# GD32F450.net
KiCad netlist of a schematic drawn in EAGLE
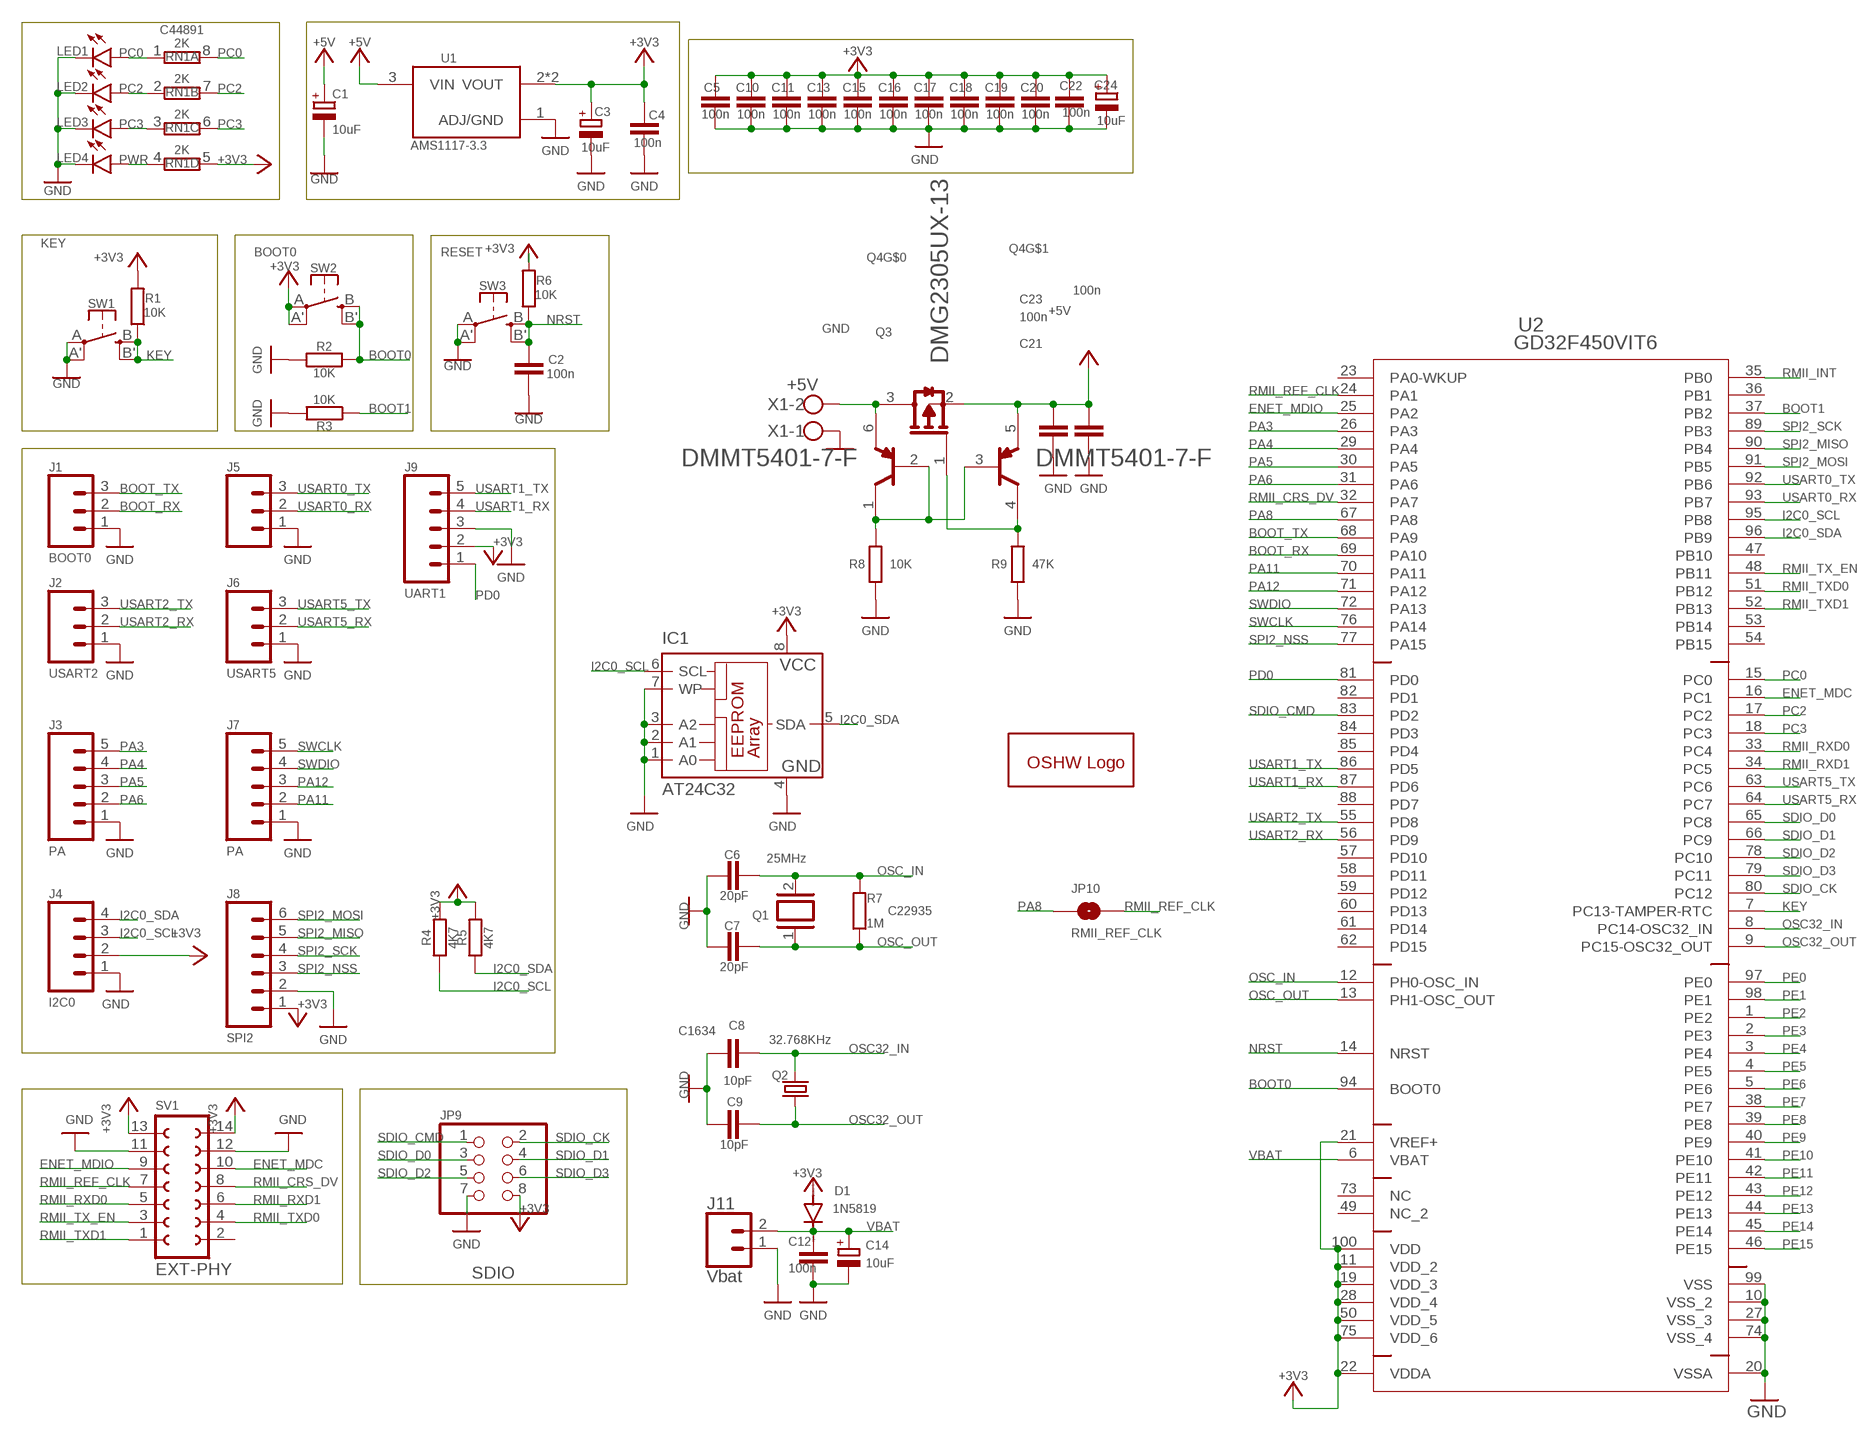
[diagram p0: schematic, sheet 1, part 1 of 2]
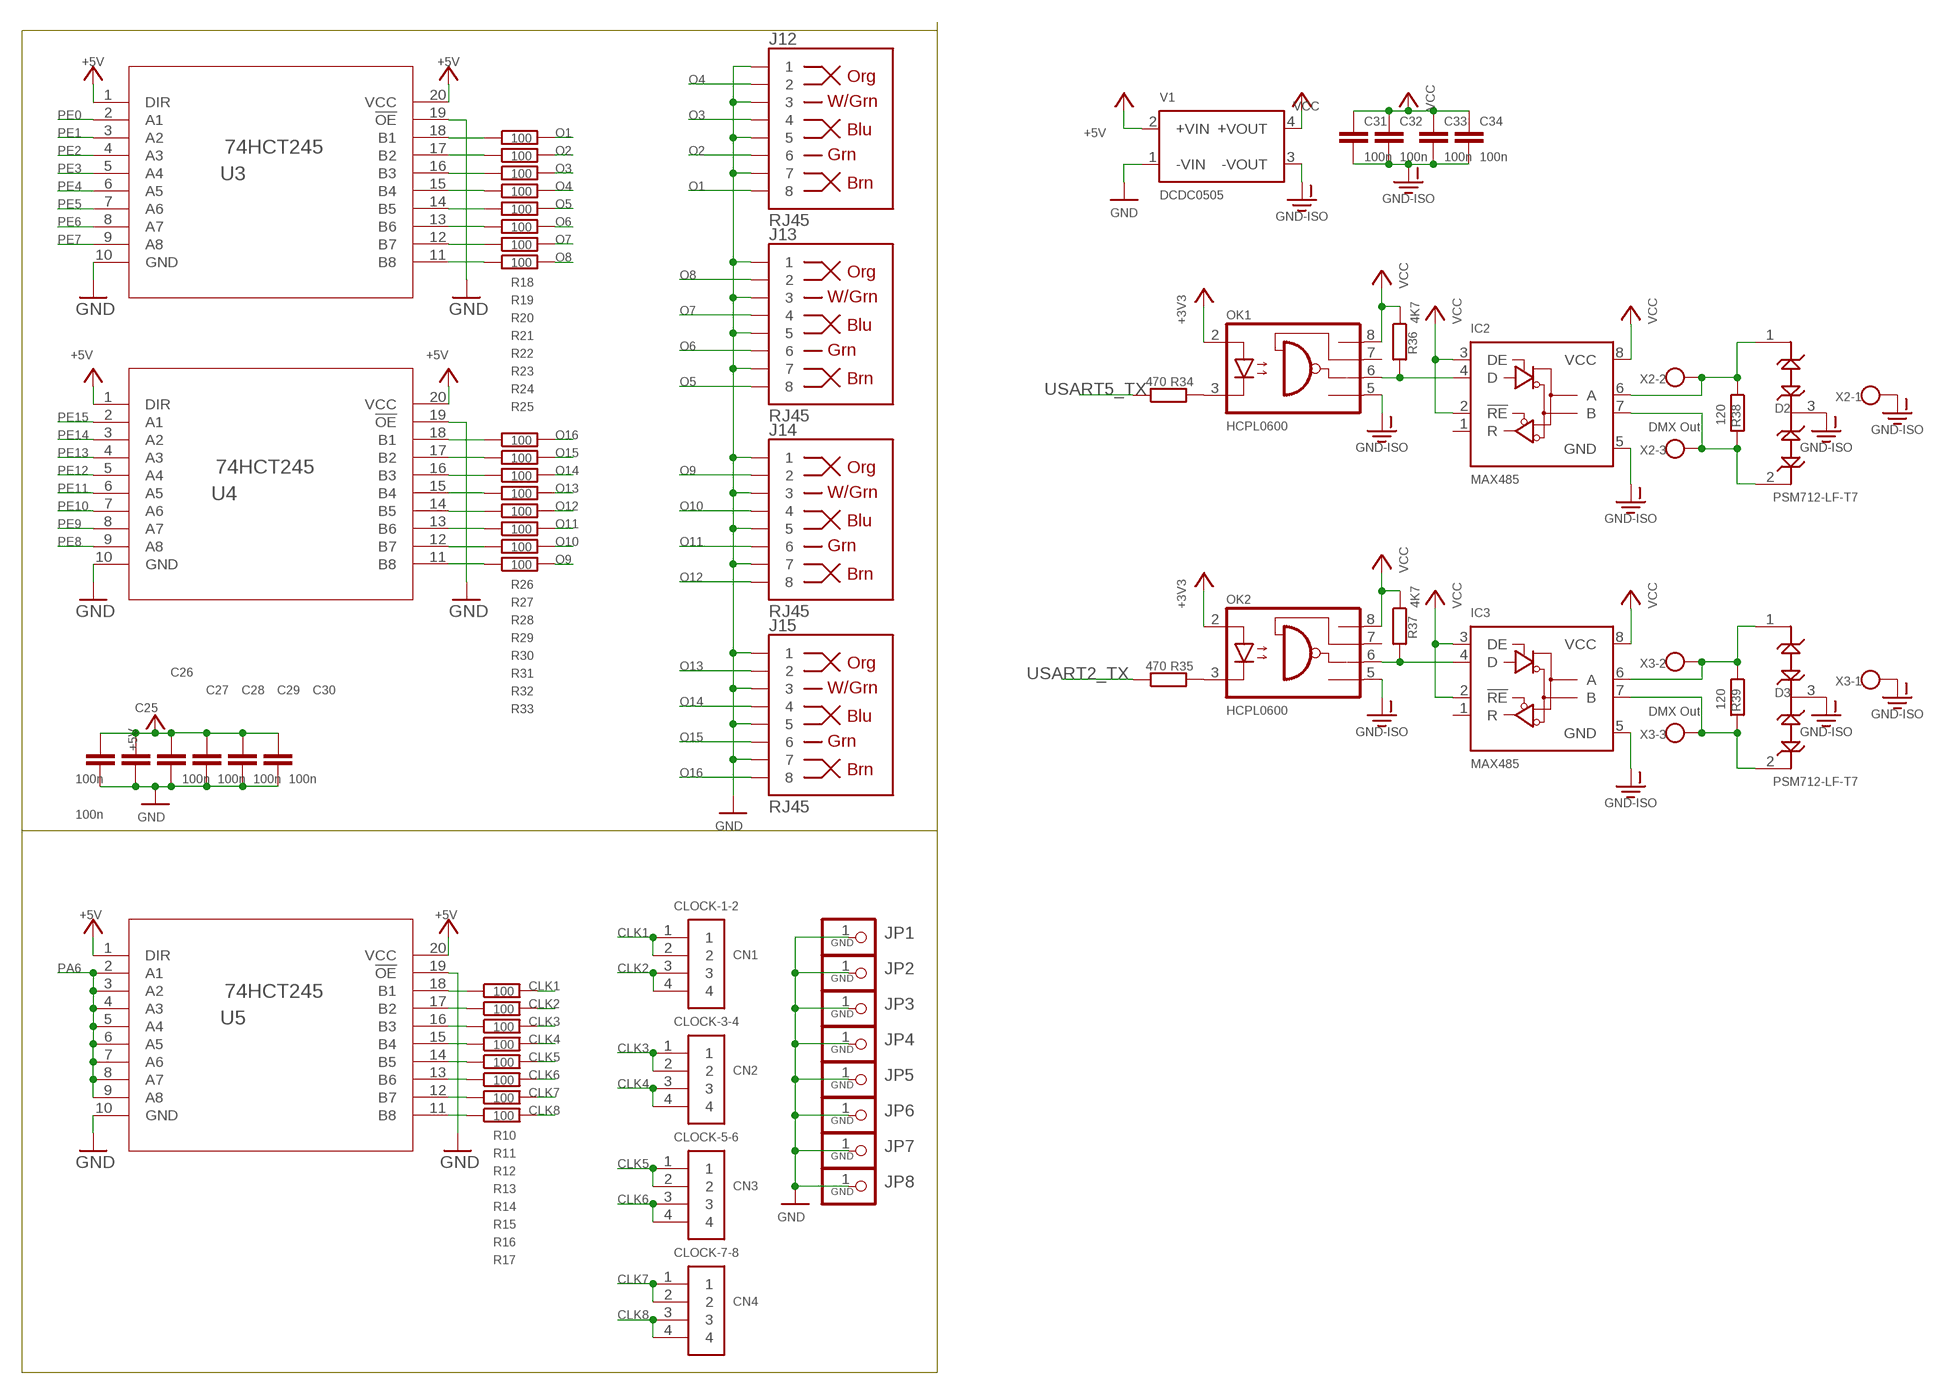
[diagram p1: schematic, sheet 1, part 2 of 2]

(export (version "E")
  (design (tool "Eeschema 10.0.6"))
  (components
    (comp (ref "C1")
      (value "10uF")
      (footprint "eagle-import:A_3216-18R")
      (libsource (lib "eagle-import") (part "CPOL-EUA/3216-18R"))
    )
    (comp (ref "C2")
      (value "100n")
      (footprint "eagle-import:C0603")
      (libsource (lib "eagle-import") (part "C-EUC0603"))
    )
    (comp (ref "C3")
      (value "10uF")
      (footprint "eagle-import:A_3216-18R")
      (libsource (lib "eagle-import") (part "CPOL-EUA/3216-18R"))
    )
    (comp (ref "C4")
      (value "100n")
      (footprint "eagle-import:C0603")
      (libsource (lib "eagle-import") (part "C-EUC0603"))
    )
    (comp (ref "C5")
      (value "100n")
      (footprint "eagle-import:C0603")
      (libsource (lib "eagle-import") (part "C-EUC0603"))
    )
    (comp (ref "C6")
      (value "20pF")
      (footprint "eagle-import:C0603")
      (libsource (lib "eagle-import") (part "C-EUC0603"))
    )
    (comp (ref "C7")
      (value "20pF")
      (footprint "eagle-import:C0603")
      (libsource (lib "eagle-import") (part "C-EUC0603"))
    )
    (comp (ref "C8")
      (value "10pF")
      (footprint "eagle-import:C0603")
      (fields (field (name "JLCPCB") "C1634"))
      (libsource (lib "eagle-import") (part "C-EUC0603"))
    )
    (comp (ref "C9")
      (value "10pF")
      (footprint "eagle-import:C0603")
      (libsource (lib "eagle-import") (part "C-EUC0603"))
    )
    (comp (ref "C10")
      (value "100n")
      (footprint "eagle-import:C0603")
      (libsource (lib "eagle-import") (part "C-EUC0603"))
    )
    (comp (ref "C11")
      (value "100n")
      (footprint "eagle-import:C0603")
      (libsource (lib "eagle-import") (part "C-EUC0603"))
    )
    (comp (ref "C12")
      (value "100n")
      (footprint "eagle-import:C0603")
      (libsource (lib "eagle-import") (part "C-EUC0603"))
    )
    (comp (ref "C13")
      (value "100n")
      (footprint "eagle-import:C0603")
      (libsource (lib "eagle-import") (part "C-EUC0603"))
    )
    (comp (ref "C14")
      (value "10uF")
      (footprint "eagle-import:A_3216-18R")
      (libsource (lib "eagle-import") (part "CPOL-EUA/3216-18R"))
    )
    (comp (ref "C15")
      (value "100n")
      (footprint "eagle-import:C0603")
      (libsource (lib "eagle-import") (part "C-EUC0603"))
    )
    (comp (ref "C16")
      (value "100n")
      (footprint "eagle-import:C0603")
      (libsource (lib "eagle-import") (part "C-EUC0603"))
    )
    (comp (ref "C17")
      (value "100n")
      (footprint "eagle-import:C0603")
      (libsource (lib "eagle-import") (part "C-EUC0603"))
    )
    (comp (ref "C18")
      (value "100n")
      (footprint "eagle-import:C0603")
      (libsource (lib "eagle-import") (part "C-EUC0603"))
    )
    (comp (ref "C19")
      (value "100n")
      (footprint "eagle-import:C0603")
      (libsource (lib "eagle-import") (part "C-EUC0603"))
    )
    (comp (ref "C20")
      (value "100n")
      (footprint "eagle-import:C0603")
      (libsource (lib "eagle-import") (part "C-EUC0603"))
    )
    (comp (ref "C21")
      (value "100n")
      (footprint "eagle-import:C0603")
      (libsource (lib "eagle-import") (part "C-EUC0603"))
    )
    (comp (ref "C22")
      (value "100n")
      (footprint "eagle-import:C0603")
      (libsource (lib "eagle-import") (part "C-EUC0603"))
    )
    (comp (ref "C23")
      (value "100n")
      (footprint "eagle-import:C0603")
      (libsource (lib "eagle-import") (part "C-EUC0603"))
    )
    (comp (ref "C24")
      (value "10uF")
      (footprint "eagle-import:A_3216-18R")
      (libsource (lib "eagle-import") (part "CPOL-EUA/3216-18R"))
    )
    (comp (ref "C25")
      (value "100n")
      (footprint "eagle-import:C0603")
      (libsource (lib "eagle-import") (part "C-EUC0603"))
    )
    (comp (ref "C26")
      (value "100n")
      (footprint "eagle-import:C0603")
      (libsource (lib "eagle-import") (part "C-EUC0603"))
    )
    (comp (ref "C27")
      (value "100n")
      (footprint "eagle-import:C0603")
      (libsource (lib "eagle-import") (part "C-EUC0603"))
    )
    (comp (ref "C28")
      (value "100n")
      (footprint "eagle-import:C0603")
      (libsource (lib "eagle-import") (part "C-EUC0603"))
    )
    (comp (ref "C29")
      (value "100n")
      (footprint "eagle-import:C0603")
      (libsource (lib "eagle-import") (part "C-EUC0603"))
    )
    (comp (ref "C30")
      (value "100n")
      (footprint "eagle-import:C0603")
      (libsource (lib "eagle-import") (part "C-EUC0603"))
    )
    (comp (ref "C31")
      (value "100n")
      (footprint "eagle-import:C0603")
      (libsource (lib "eagle-import") (part "C-EUC0603"))
    )
    (comp (ref "C32")
      (value "100n")
      (footprint "eagle-import:C0603")
      (libsource (lib "eagle-import") (part "C-EUC0603"))
    )
    (comp (ref "C33")
      (value "100n")
      (footprint "eagle-import:C0603")
      (libsource (lib "eagle-import") (part "C-EUC0603"))
    )
    (comp (ref "C34")
      (value "100n")
      (footprint "eagle-import:C0603")
      (libsource (lib "eagle-import") (part "C-EUC0603"))
    )
    (comp (ref "CN1")
      (value "CLOCK-1-2")
      (footprint "eagle-import:1X04-CLEANBIG")
      (libsource (lib "eagle-import") (part "1X4-CLEANBIG"))
    )
    (comp (ref "CN2")
      (value "CLOCK-3-4")
      (footprint "eagle-import:1X04-CLEANBIG")
      (libsource (lib "eagle-import") (part "1X4-CLEANBIG"))
    )
    (comp (ref "CN3")
      (value "CLOCK-5-6")
      (footprint "eagle-import:1X04-CLEANBIG")
      (libsource (lib "eagle-import") (part "1X4-CLEANBIG"))
    )
    (comp (ref "CN4")
      (value "CLOCK-7-8")
      (footprint "eagle-import:1X04-CLEANBIG")
      (libsource (lib "eagle-import") (part "1X4-CLEANBIG"))
    )
    (comp (ref "D1")
      (value "1N5819")
      (footprint "eagle-import:SOD323-R")
      (libsource (lib "eagle-import") (part "DIODE-SOD323-R"))
    )
    (comp (ref "D2")
      (value "PSM712-LF-T7")
      (footprint "eagle-import:SOT23-3")
      (libsource (lib "eagle-import") (part "2CH_BI_DIR_TVSSOT23"))
    )
    (comp (ref "D3")
      (value "PSM712-LF-T7")
      (footprint "eagle-import:SOT23-3")
      (libsource (lib "eagle-import") (part "2CH_BI_DIR_TVSSOT23"))
    )
    (comp (ref "GOLD_ORB_SM1")
      (value "OSHWLOGOLOGO5MM")
      (footprint "eagle-import:OSHW_5MM")
      (libsource (lib "eagle-import") (part "OSHWLOGOLOGO5MM"))
    )
    (comp (ref "IC1")
      (value "AT24C32")
      (footprint "eagle-import:SO-08M")
      (fields (field (name "MPN") "M24C04-WMN6P"))
      (libsource (lib "eagle-import") (part "24SMC04A"))
    )
    (comp (ref "IC2")
      (value "MAX485")
      (footprint "eagle-import:D_R-PDSO-G8")
      (libsource (lib "eagle-import") (part "75176AD"))
    )
    (comp (ref "IC3")
      (value "MAX485")
      (footprint "eagle-import:D_R-PDSO-G8")
      (libsource (lib "eagle-import") (part "75176AD"))
    )
    (comp (ref "J1")
      (value "BOOT0")
      (footprint "eagle-import:1X03")
      (libsource (lib "eagle-import") (part "CONN_03"))
    )
    (comp (ref "J2")
      (value "USART2")
      (footprint "eagle-import:1X03")
      (libsource (lib "eagle-import") (part "CONN_03"))
    )
    (comp (ref "J3")
      (value "PA")
      (footprint "eagle-import:1X05")
      (libsource (lib "eagle-import") (part "CONN_05"))
    )
    (comp (ref "J4")
      (value "I2C0")
      (footprint "eagle-import:1X04")
      (libsource (lib "eagle-import") (part "CONN_04"))
    )
    (comp (ref "J5")
      (value "USART0")
      (footprint "eagle-import:1X03")
      (libsource (lib "eagle-import") (part "CONN_03"))
    )
    (comp (ref "J6")
      (value "USART5")
      (footprint "eagle-import:1X03")
      (libsource (lib "eagle-import") (part "CONN_03"))
    )
    (comp (ref "J7")
      (value "PA")
      (footprint "eagle-import:1X05")
      (libsource (lib "eagle-import") (part "CONN_05"))
    )
    (comp (ref "J8")
      (value "SPI2")
      (footprint "eagle-import:1X06")
      (libsource (lib "eagle-import") (part "CONN_06SILK_FEMALE_PTH"))
    )
    (comp (ref "J9")
      (value "UART1")
      (footprint "eagle-import:1X05")
      (libsource (lib "eagle-import") (part "CONN_05"))
    )
    (comp (ref "J11")
      (value "Vbat")
      (footprint "eagle-import:1X02_NO_SILK")
      (libsource (lib "eagle-import") (part "CONN_021X02_NO_SILK"))
    )
    (comp (ref "J12")
      (value "RJ45")
      (footprint "eagle-import:RJ45-8")
      (libsource (lib "eagle-import") (part "RJ45-8"))
    )
    (comp (ref "J13")
      (value "RJ45")
      (footprint "eagle-import:RJ45-8")
      (libsource (lib "eagle-import") (part "RJ45-8"))
    )
    (comp (ref "J14")
      (value "RJ45")
      (footprint "eagle-import:RJ45-8")
      (libsource (lib "eagle-import") (part "RJ45-8"))
    )
    (comp (ref "J15")
      (value "RJ45")
      (footprint "eagle-import:RJ45-8")
      (libsource (lib "eagle-import") (part "RJ45-8"))
    )
    (comp (ref "JP1")
      (value "GND")
      (footprint "eagle-import:1X01-CLEANBIG")
      (libsource (lib "eagle-import") (part "PINHD-1X1CB"))
    )
    (comp (ref "JP2")
      (value "GND")
      (footprint "eagle-import:1X01-CLEANBIG")
      (libsource (lib "eagle-import") (part "PINHD-1X1CB"))
    )
    (comp (ref "JP3")
      (value "GND")
      (footprint "eagle-import:1X01-CLEANBIG")
      (libsource (lib "eagle-import") (part "PINHD-1X1CB"))
    )
    (comp (ref "JP4")
      (value "GND")
      (footprint "eagle-import:1X01-CLEANBIG")
      (libsource (lib "eagle-import") (part "PINHD-1X1CB"))
    )
    (comp (ref "JP5")
      (value "GND")
      (footprint "eagle-import:1X01-CLEANBIG")
      (libsource (lib "eagle-import") (part "PINHD-1X1CB"))
    )
    (comp (ref "JP6")
      (value "GND")
      (footprint "eagle-import:1X01-CLEANBIG")
      (libsource (lib "eagle-import") (part "PINHD-1X1CB"))
    )
    (comp (ref "JP7")
      (value "GND")
      (footprint "eagle-import:1X01-CLEANBIG")
      (libsource (lib "eagle-import") (part "PINHD-1X1CB"))
    )
    (comp (ref "JP8")
      (value "GND")
      (footprint "eagle-import:1X01-CLEANBIG")
      (libsource (lib "eagle-import") (part "PINHD-1X1CB"))
    )
    (comp (ref "JP9")
      (value "SDIO")
      (footprint "eagle-import:2X04")
      (libsource (lib "eagle-import") (part "PINHD-2X4"))
    )
    (comp (ref "JP10")
      (value "RMII_REF_CLK")
      (footprint "eagle-import:SMT-JUMPER_2_NO_NO-SILK")
      (libsource (lib "eagle-import") (part "JUMPER-SMT_2_NO_NO-SILK"))
    )
    (comp (ref "LED1")
      (value "PC0")
      (footprint "eagle-import:CHIP-LED0603")
      (libsource (lib "eagle-import") (part "LEDCHIP-LED0603"))
    )
    (comp (ref "LED2")
      (value "PC2")
      (footprint "eagle-import:CHIP-LED0603")
      (libsource (lib "eagle-import") (part "LEDCHIP-LED0603"))
    )
    (comp (ref "LED3")
      (value "PC3")
      (footprint "eagle-import:CHIP-LED0603")
      (libsource (lib "eagle-import") (part "LEDCHIP-LED0603"))
    )
    (comp (ref "LED4")
      (value "PWR")
      (footprint "eagle-import:CHIP-LED0603")
      (libsource (lib "eagle-import") (part "LEDCHIP-LED0603"))
    )
    (comp (ref "OK1")
      (value "HCPL0600")
      (footprint "eagle-import:SOIC08")
      (fields (field (name "MF") "AGILENT TECHNOLOGIES") (field (name "MPN") "HCPL-0600-000E"))
      (libsource (lib "eagle-import") (part "HCPL0600"))
    )
    (comp (ref "OK2")
      (value "HCPL0600")
      (footprint "eagle-import:SOIC08")
      (fields (field (name "MF") "AGILENT TECHNOLOGIES") (field (name "MPN") "HCPL-0600-000E"))
      (libsource (lib "eagle-import") (part "HCPL0600"))
    )
    (comp (ref "Q1")
      (value "25MHz")
      (footprint "eagle-import:QS")
      (libsource (lib "eagle-import") (part "XTAL/S"))
    )
    (comp (ref "Q2")
      (value "32.768KHz")
      (footprint "eagle-import:TC26H")
      (libsource (lib "eagle-import") (part "CRYSTALTC26H"))
    )
    (comp (ref "Q3")
      (value "DMG2305UX")
      (footprint "eagle-import:DIODES_INC._DMG2305UX-13_0")
      (fields
        (field (name "DIGIKEY_PART_NUMBER") "DMG2305UX-13DICT-ND")
        (field (name "MF") "Diodes Inc.")
        (field (name "MOUSER_PART_NUMBER") "621-DMG2305UX-13")
      )
      (libsource (lib "eagle-import") (part "DIODES_INC._DMG2305UX-13DIODES_INC._DMG2305UX-13_0_0"))
    )
    (comp (ref "Q4")
      (value "DMMT5401")
      (footprint "eagle-import:DIODES_DMMT5401-7-F_0")
      (fields
        (field (name "DIGIKEY_PART_NUMBER") "DMMT5401-FDICT-ND")
        (field (name "MF") "Diodes")
        (field (name "MOUSER_PART_NUMBER") "621-DMMT5401-7-F")
      )
      (libsource (lib "eagle-import") (part "DIODES_DMMT5401-7-FDIODES_DMMT5401-7-F_0_0"))
    )
    (comp (ref "R1")
      (value "10K")
      (footprint "eagle-import:R0603")
      (libsource (lib "eagle-import") (part "R-EU_R0603"))
    )
    (comp (ref "R2")
      (value "10K")
      (footprint "eagle-import:R0603")
      (libsource (lib "eagle-import") (part "R-EU_R0603"))
    )
    (comp (ref "R3")
      (value "10K")
      (footprint "eagle-import:R0603")
      (libsource (lib "eagle-import") (part "R-EU_R0603"))
    )
    (comp (ref "R4")
      (value "4K7")
      (footprint "eagle-import:R0402")
      (libsource (lib "eagle-import") (part "R-EU_R0402"))
    )
    (comp (ref "R5")
      (value "4K7")
      (footprint "eagle-import:R0402")
      (libsource (lib "eagle-import") (part "R-EU_R0402"))
    )
    (comp (ref "R6")
      (value "10K")
      (footprint "eagle-import:R0603")
      (libsource (lib "eagle-import") (part "R-EU_R0603"))
    )
    (comp (ref "R7")
      (value "1M")
      (footprint "eagle-import:R0603")
      (fields (field (name "JLCPCB") "C22935"))
      (libsource (lib "eagle-import") (part "R-EU_R0603"))
    )
    (comp (ref "R8")
      (value "10K")
      (footprint "eagle-import:R0402")
      (libsource (lib "eagle-import") (part "R-EU_R0402"))
    )
    (comp (ref "R9")
      (value "47K")
      (footprint "eagle-import:R0402")
      (libsource (lib "eagle-import") (part "R-EU_R0402"))
    )
    (comp (ref "R10")
      (value "100")
      (footprint "eagle-import:R0402")
      (libsource (lib "eagle-import") (part "R-EU_R0402"))
    )
    (comp (ref "R11")
      (value "100")
      (footprint "eagle-import:R0402")
      (libsource (lib "eagle-import") (part "R-EU_R0402"))
    )
    (comp (ref "R12")
      (value "100")
      (footprint "eagle-import:R0402")
      (libsource (lib "eagle-import") (part "R-EU_R0402"))
    )
    (comp (ref "R13")
      (value "100")
      (footprint "eagle-import:R0402")
      (libsource (lib "eagle-import") (part "R-EU_R0402"))
    )
    (comp (ref "R14")
      (value "100")
      (footprint "eagle-import:R0402")
      (libsource (lib "eagle-import") (part "R-EU_R0402"))
    )
    (comp (ref "R15")
      (value "100")
      (footprint "eagle-import:R0402")
      (libsource (lib "eagle-import") (part "R-EU_R0402"))
    )
    (comp (ref "R16")
      (value "100")
      (footprint "eagle-import:R0402")
      (libsource (lib "eagle-import") (part "R-EU_R0402"))
    )
    (comp (ref "R17")
      (value "100")
      (footprint "eagle-import:R0402")
      (libsource (lib "eagle-import") (part "R-EU_R0402"))
    )
    (comp (ref "R18")
      (value "100")
      (footprint "eagle-import:R0402")
      (libsource (lib "eagle-import") (part "R-EU_R0402"))
    )
    (comp (ref "R19")
      (value "100")
      (footprint "eagle-import:R0402")
      (libsource (lib "eagle-import") (part "R-EU_R0402"))
    )
    (comp (ref "R20")
      (value "100")
      (footprint "eagle-import:R0402")
      (libsource (lib "eagle-import") (part "R-EU_R0402"))
    )
    (comp (ref "R21")
      (value "100")
      (footprint "eagle-import:R0402")
      (libsource (lib "eagle-import") (part "R-EU_R0402"))
    )
    (comp (ref "R22")
      (value "100")
      (footprint "eagle-import:R0402")
      (libsource (lib "eagle-import") (part "R-EU_R0402"))
    )
    (comp (ref "R23")
      (value "100")
      (footprint "eagle-import:R0402")
      (libsource (lib "eagle-import") (part "R-EU_R0402"))
    )
    (comp (ref "R24")
      (value "100")
      (footprint "eagle-import:R0402")
      (libsource (lib "eagle-import") (part "R-EU_R0402"))
    )
    (comp (ref "R25")
      (value "100")
      (footprint "eagle-import:R0402")
      (libsource (lib "eagle-import") (part "R-EU_R0402"))
    )
    (comp (ref "R26")
      (value "100")
      (footprint "eagle-import:R0402")
      (libsource (lib "eagle-import") (part "R-EU_R0402"))
    )
    (comp (ref "R27")
      (value "100")
      (footprint "eagle-import:R0402")
      (libsource (lib "eagle-import") (part "R-EU_R0402"))
    )
    (comp (ref "R28")
      (value "100")
      (footprint "eagle-import:R0402")
      (libsource (lib "eagle-import") (part "R-EU_R0402"))
    )
    (comp (ref "R29")
      (value "100")
      (footprint "eagle-import:R0402")
      (libsource (lib "eagle-import") (part "R-EU_R0402"))
    )
    (comp (ref "R30")
      (value "100")
      (footprint "eagle-import:R0402")
      (libsource (lib "eagle-import") (part "R-EU_R0402"))
    )
    (comp (ref "R31")
      (value "100")
      (footprint "eagle-import:R0402")
      (libsource (lib "eagle-import") (part "R-EU_R0402"))
    )
    (comp (ref "R32")
      (value "100")
      (footprint "eagle-import:R0402")
      (libsource (lib "eagle-import") (part "R-EU_R0402"))
    )
    (comp (ref "R33")
      (value "100")
      (footprint "eagle-import:R0402")
      (libsource (lib "eagle-import") (part "R-EU_R0402"))
    )
    (comp (ref "R34")
      (value "470")
      (footprint "eagle-import:R0402")
      (libsource (lib "eagle-import") (part "R-EU_R0402"))
    )
    (comp (ref "R35")
      (value "470")
      (footprint "eagle-import:R0402")
      (libsource (lib "eagle-import") (part "R-EU_R0402"))
    )
    (comp (ref "R36")
      (value "4K7")
      (footprint "eagle-import:R0402")
      (libsource (lib "eagle-import") (part "R-EU_R0402"))
    )
    (comp (ref "R37")
      (value "4K7")
      (footprint "eagle-import:R0402")
      (libsource (lib "eagle-import") (part "R-EU_R0402"))
    )
    (comp (ref "R38")
      (value "120")
      (footprint "eagle-import:R0402")
      (libsource (lib "eagle-import") (part "R-EU_R0402"))
    )
    (comp (ref "R39")
      (value "120")
      (footprint "eagle-import:R0402")
      (libsource (lib "eagle-import") (part "R-EU_R0402"))
    )
    (comp (ref "RN1")
      (value "2K")
      (footprint "eagle-import:4X0402ARV341")
      (fields (field (name "JLCPCB") "C44891"))
      (libsource (lib "eagle-import") (part "4R-N0402ARV341"))
    )
    (comp (ref "SV1")
      (value "EXT-PHY")
      (footprint "eagle-import:FE07-2W")
      (libsource (lib "eagle-import") (part "FE07-2W"))
    )
    (comp (ref "SW1")
      (value "KEY")
      (footprint "eagle-import:EVQ-Q2")
      (libsource (lib "eagle-import") (part "SPST_TACT-EVQQ2"))
    )
    (comp (ref "SW2")
      (value "BOOT0")
      (footprint "eagle-import:EVQ-Q2")
      (libsource (lib "eagle-import") (part "SPST_TACT-EVQQ2"))
    )
    (comp (ref "SW3")
      (value "RESET")
      (footprint "eagle-import:EVQ-Q2")
      (libsource (lib "eagle-import") (part "SPST_TACT-EVQQ2"))
    )
    (comp (ref "U1")
      (value "AMS1117-3.3")
      (footprint "eagle-import:SOT229P700X180-4N")
      (fields (field (name "JLCPCB_PART_NUMBER") "C6186") (field (name "MF") "Advanced Monolithic Systems"))
      (libsource (lib "eagle-import") (part "AMS1117-3.3"))
    )
    (comp (ref "U2")
      (value "GD32F450VIT6")
      (footprint "eagle-import:LQFP100")
      (fields
        (field (name "MANUFACTURER_PART_NUMBER") "GD32F450VET6")
        (field (name "COPYRIGHT") "Copyright (C) 2022 Ultra Librarian. All rights reserved.")
      )
      (libsource (lib "eagle-import") (part "GD32F450VET6"))
    )
    (comp (ref "U3")
      (value "74HCT245")
      (footprint "eagle-import:PW20")
      (fields
        (field (name "GENERIC_PART_NUMBER") "SN74HCT245")
        (field (name "MANUFACTURER") "Texas Instruments")
        (field (name "MANUFACTURER_PART_NUMBER") "SN74HCT245PWR")
      )
      (libsource (lib "eagle-import") (part "SN74HCT245PWR"))
    )
    (comp (ref "U4")
      (value "74HCT245")
      (footprint "eagle-import:PW20")
      (fields
        (field (name "GENERIC_PART_NUMBER") "SN74HCT245")
        (field (name "MANUFACTURER") "Texas Instruments")
        (field (name "MANUFACTURER_PART_NUMBER") "SN74HCT245PWR")
      )
      (libsource (lib "eagle-import") (part "SN74HCT245PWR"))
    )
    (comp (ref "U5")
      (value "74HCT245")
      (footprint "eagle-import:PW20")
      (fields
        (field (name "GENERIC_PART_NUMBER") "SN74HCT245")
        (field (name "MANUFACTURER") "Texas Instruments")
        (field (name "MANUFACTURER_PART_NUMBER") "SN74HCT245PWR")
      )
      (libsource (lib "eagle-import") (part "SN74HCT245PWR"))
    )
    (comp (ref "V1")
      (value "DCDC0505")
      (footprint "eagle-import:TME")
      (fields (field (name "MPN") "TME 0505S"))
      (libsource (lib "eagle-import") (part "TME?0505S"))
    )
    (comp (ref "X1")
      (value "+5V")
      (footprint "eagle-import:W237-102")
      (fields (field (name "MPN") "237-102"))
      (libsource (lib "eagle-import") (part "W237-102"))
    )
    (comp (ref "X2")
      (value "DMX Out")
      (footprint "eagle-import:W237-103")
      (fields (field (name "MPN") "237-103"))
      (libsource (lib "eagle-import") (part "W237-103"))
    )
    (comp (ref "X3")
      (value "DMX Out")
      (footprint "eagle-import:W237-103")
      (fields (field (name "MPN") "237-103"))
      (libsource (lib "eagle-import") (part "W237-103"))
    )
  )
  (nets
    (net (code "1") (name "+3V3") (class "Default")
      (node (ref "C10") (pin "1") (pinfunction "1_1") (pintype "passive"))
      (node (ref "C11") (pin "1") (pinfunction "1_1") (pintype "passive"))
      (node (ref "C13") (pin "1") (pinfunction "1_1") (pintype "passive"))
      (node (ref "C15") (pin "1") (pinfunction "1_1") (pintype "passive"))
      (node (ref "C16") (pin "1") (pinfunction "1_1") (pintype "passive"))
      (node (ref "C17") (pin "1") (pinfunction "1_1") (pintype "passive"))
      (node (ref "C18") (pin "1") (pinfunction "1_1") (pintype "passive"))
      (node (ref "C19") (pin "1") (pinfunction "1_1") (pintype "passive"))
      (node (ref "C20") (pin "1") (pinfunction "1_1") (pintype "passive"))
      (node (ref "C22") (pin "1") (pinfunction "1_1") (pintype "passive"))
      (node (ref "C24") (pin "+") (pinfunction "+_+") (pintype "passive"))
      (node (ref "C3") (pin "+") (pinfunction "+_+") (pintype "passive"))
      (node (ref "C4") (pin "1") (pinfunction "1_1") (pintype "passive"))
      (node (ref "C5") (pin "1") (pinfunction "1_1") (pintype "passive"))
      (node (ref "D1") (pin "A") (pinfunction "A_A") (pintype "passive"))
      (node (ref "IC1") (pin "8") (pinfunction "VCC_8") (pintype "power_in"))
      (node (ref "J4") (pin "2") (pinfunction "2_2") (pintype "passive"))
      (node (ref "J8") (pin "1") (pinfunction "1_1") (pintype "passive"))
      (node (ref "J9") (pin "2") (pinfunction "2_2") (pintype "passive"))
      (node (ref "JP9") (pin "8") (pinfunction "8_8") (pintype "passive"))
      (node (ref "OK1") (pin "2") (pinfunction "A_2") (pintype "passive"))
      (node (ref "OK2") (pin "2") (pinfunction "A_2") (pintype "passive"))
      (node (ref "R1") (pin "2") (pinfunction "2_2") (pintype "passive"))
      (node (ref "R4") (pin "2") (pinfunction "2_2") (pintype "passive"))
      (node (ref "R5") (pin "2") (pinfunction "2_2") (pintype "passive"))
      (node (ref "R6") (pin "2") (pinfunction "2_2") (pintype "passive"))
      (node (ref "RN1") (pin "5") (pinfunction "2_5") (pintype "passive"))
      (node (ref "SV1") (pin "13") (pinfunction "13_13") (pintype "passive"))
      (node (ref "SV1") (pin "14") (pinfunction "14_14") (pintype "passive"))
      (node (ref "SW2") (pin "A") (pinfunction "P_A") (pintype "passive"))
      (node (ref "SW2") (pin "A'") (pinfunction "P1_A'") (pintype "passive"))
      (node (ref "U1") (pin "2") (pinfunction "VOUT_2") (pintype "output"))
      (node (ref "U1") (pin "4") (pinfunction "VOUT_4") (pintype "output"))
      (node (ref "U2") (pin "100") (pinfunction "VDD_100") (pintype "power_in"))
      (node (ref "U2") (pin "11") (pinfunction "VDD_2_11") (pintype "power_in"))
      (node (ref "U2") (pin "19") (pinfunction "VDD_3_19") (pintype "power_in"))
      (node (ref "U2") (pin "21") (pinfunction "VREF+_21") (pintype "power_in"))
      (node (ref "U2") (pin "22") (pinfunction "VDDA_22") (pintype "power_in"))
      (node (ref "U2") (pin "28") (pinfunction "VDD_4_28") (pintype "power_in"))
      (node (ref "U2") (pin "50") (pinfunction "VDD_5_50") (pintype "power_in"))
      (node (ref "U2") (pin "75") (pinfunction "VDD_6_75") (pintype "power_in"))
    )
    (net (code "2") (name "+5V") (class "Default")
      (node (ref "C1") (pin "+") (pinfunction "+_+") (pintype "passive"))
      (node (ref "C21") (pin "1") (pinfunction "1_1") (pintype "passive"))
      (node (ref "C23") (pin "1") (pinfunction "1_1") (pintype "passive"))
      (node (ref "C25") (pin "1") (pinfunction "1_1") (pintype "passive"))
      (node (ref "C26") (pin "1") (pinfunction "1_1") (pintype "passive"))
      (node (ref "C27") (pin "1") (pinfunction "1_1") (pintype "passive"))
      (node (ref "C28") (pin "1") (pinfunction "1_1") (pintype "passive"))
      (node (ref "C29") (pin "1") (pinfunction "1_1") (pintype "passive"))
      (node (ref "C30") (pin "1") (pinfunction "1_1") (pintype "passive"))
      (node (ref "Q3") (pin "2") (pinfunction "S_2") (pintype "passive"))
      (node (ref "Q4") (pin "5") (pinfunction "E2_5") (pintype "passive"))
      (node (ref "U1") (pin "3") (pinfunction "VIN_3") (pintype "input"))
      (node (ref "U3") (pin "1") (pinfunction "DIR_1") (pintype "input"))
      (node (ref "U3") (pin "20") (pinfunction "VCC_20") (pintype "power_in"))
      (node (ref "U4") (pin "1") (pinfunction "DIR_1") (pintype "input"))
      (node (ref "U4") (pin "20") (pinfunction "VCC_20") (pintype "power_in"))
      (node (ref "U5") (pin "1") (pinfunction "DIR_1") (pintype "input"))
      (node (ref "U5") (pin "20") (pinfunction "VCC_20") (pintype "power_in"))
      (node (ref "V1") (pin "2") (pinfunction "+VIN_2") (pintype "passive"))
    )
    (net (code "3") (name "/BOOT0") (class "Default")
      (node (ref "R2") (pin "2") (pinfunction "2_2") (pintype "passive"))
      (node (ref "SW2") (pin "B") (pinfunction "S_B") (pintype "passive"))
      (node (ref "SW2") (pin "B'") (pinfunction "S1_B'") (pintype "passive"))
      (node (ref "U2") (pin "94") (pinfunction "BOOT0_94") (pintype "input"))
    )
    (net (code "4") (name "/BOOT1") (class "Default")
      (node (ref "R3") (pin "1") (pinfunction "1_1") (pintype "passive"))
      (node (ref "U2") (pin "37") (pinfunction "PB2_37") (pintype "bidirectional"))
    )
    (net (code "5") (name "/BOOT_RX") (class "Default")
      (node (ref "J1") (pin "2") (pinfunction "2_2") (pintype "passive"))
      (node (ref "U2") (pin "69") (pinfunction "PA10_69") (pintype "bidirectional"))
    )
    (net (code "6") (name "/BOOT_TX") (class "Default")
      (node (ref "J1") (pin "3") (pinfunction "3_3") (pintype "passive"))
      (node (ref "U2") (pin "68") (pinfunction "PA9_68") (pintype "bidirectional"))
    )
    (net (code "7") (name "/CLK1") (class "Default")
      (node (ref "CN1") (pin "1") (pinfunction "1_1") (pintype "bidirectional"))
      (node (ref "CN1") (pin "2") (pinfunction "2_2") (pintype "bidirectional"))
      (node (ref "R10") (pin "2") (pinfunction "2_2") (pintype "passive"))
    )
    (net (code "8") (name "/CLK2") (class "Default")
      (node (ref "CN1") (pin "3") (pinfunction "3_3") (pintype "bidirectional"))
      (node (ref "CN1") (pin "4") (pinfunction "4_4") (pintype "bidirectional"))
      (node (ref "R11") (pin "2") (pinfunction "2_2") (pintype "passive"))
    )
    (net (code "9") (name "/CLK3") (class "Default")
      (node (ref "CN2") (pin "1") (pinfunction "1_1") (pintype "bidirectional"))
      (node (ref "CN2") (pin "2") (pinfunction "2_2") (pintype "bidirectional"))
      (node (ref "R12") (pin "2") (pinfunction "2_2") (pintype "passive"))
    )
    (net (code "10") (name "/CLK4") (class "Default")
      (node (ref "CN2") (pin "3") (pinfunction "3_3") (pintype "bidirectional"))
      (node (ref "CN2") (pin "4") (pinfunction "4_4") (pintype "bidirectional"))
      (node (ref "R13") (pin "2") (pinfunction "2_2") (pintype "passive"))
    )
    (net (code "11") (name "/CLK5") (class "Default")
      (node (ref "CN3") (pin "1") (pinfunction "1_1") (pintype "bidirectional"))
      (node (ref "CN3") (pin "2") (pinfunction "2_2") (pintype "bidirectional"))
      (node (ref "R14") (pin "2") (pinfunction "2_2") (pintype "passive"))
    )
    (net (code "12") (name "/CLK6") (class "Default")
      (node (ref "CN3") (pin "3") (pinfunction "3_3") (pintype "bidirectional"))
      (node (ref "CN3") (pin "4") (pinfunction "4_4") (pintype "bidirectional"))
      (node (ref "R15") (pin "2") (pinfunction "2_2") (pintype "passive"))
    )
    (net (code "13") (name "/CLK7") (class "Default")
      (node (ref "CN4") (pin "1") (pinfunction "1_1") (pintype "bidirectional"))
      (node (ref "CN4") (pin "2") (pinfunction "2_2") (pintype "bidirectional"))
      (node (ref "R16") (pin "2") (pinfunction "2_2") (pintype "passive"))
    )
    (net (code "14") (name "/CLK8") (class "Default")
      (node (ref "CN4") (pin "3") (pinfunction "3_3") (pintype "bidirectional"))
      (node (ref "CN4") (pin "4") (pinfunction "4_4") (pintype "bidirectional"))
      (node (ref "R17") (pin "2") (pinfunction "2_2") (pintype "passive"))
    )
    (net (code "15") (name "/ENET_MDC") (class "Default")
      (node (ref "SV1") (pin "10") (pinfunction "10_10") (pintype "passive"))
      (node (ref "U2") (pin "16") (pinfunction "PC1_16") (pintype "bidirectional"))
    )
    (net (code "16") (name "/ENET_MDIO") (class "Default")
      (node (ref "SV1") (pin "9") (pinfunction "9_9") (pintype "passive"))
      (node (ref "U2") (pin "25") (pinfunction "PA2_25") (pintype "bidirectional"))
    )
    (net (code "17") (name "/I2C0_SCL") (class "Default")
      (node (ref "IC1") (pin "6") (pinfunction "SCL_6") (pintype "input"))
      (node (ref "J4") (pin "3") (pinfunction "3_3") (pintype "passive"))
      (node (ref "R4") (pin "1") (pinfunction "1_1") (pintype "passive"))
      (node (ref "U2") (pin "95") (pinfunction "PB8_95") (pintype "bidirectional"))
    )
    (net (code "18") (name "/I2C0_SDA") (class "Default")
      (node (ref "IC1") (pin "5") (pinfunction "SDA_5") (pintype "bidirectional"))
      (node (ref "J4") (pin "4") (pinfunction "4_4") (pintype "passive"))
      (node (ref "R5") (pin "1") (pinfunction "1_1") (pintype "passive"))
      (node (ref "U2") (pin "96") (pinfunction "PB9_96") (pintype "bidirectional"))
    )
    (net (code "19") (name "/KEY") (class "Default")
      (node (ref "R1") (pin "1") (pinfunction "1_1") (pintype "passive"))
      (node (ref "SW1") (pin "B") (pinfunction "S_B") (pintype "passive"))
      (node (ref "SW1") (pin "B'") (pinfunction "S1_B'") (pintype "passive"))
      (node (ref "U2") (pin "7") (pinfunction "PC13-TAMPER-RTC_7") (pintype "bidirectional"))
    )
    (net (code "20") (name "/NRST") (class "Default")
      (node (ref "C2") (pin "1") (pinfunction "1_1") (pintype "passive"))
      (node (ref "R6") (pin "1") (pinfunction "1_1") (pintype "passive"))
      (node (ref "SW3") (pin "B") (pinfunction "S_B") (pintype "passive"))
      (node (ref "SW3") (pin "B'") (pinfunction "S1_B'") (pintype "passive"))
      (node (ref "U2") (pin "14") (pinfunction "NRST_14") (pintype "bidirectional"))
    )
    (net (code "21") (name "/O1") (class "Default")
      (node (ref "J12") (pin "8") (pinfunction "8_8") (pintype "bidirectional"))
      (node (ref "R18") (pin "2") (pinfunction "2_2") (pintype "passive"))
    )
    (net (code "22") (name "/O2") (class "Default")
      (node (ref "J12") (pin "6") (pinfunction "6_6") (pintype "bidirectional"))
      (node (ref "R19") (pin "2") (pinfunction "2_2") (pintype "passive"))
    )
    (net (code "23") (name "/O3") (class "Default")
      (node (ref "J12") (pin "4") (pinfunction "4_4") (pintype "bidirectional"))
      (node (ref "R20") (pin "2") (pinfunction "2_2") (pintype "passive"))
    )
    (net (code "24") (name "/O4") (class "Default")
      (node (ref "J12") (pin "2") (pinfunction "2_2") (pintype "bidirectional"))
      (node (ref "R21") (pin "2") (pinfunction "2_2") (pintype "passive"))
    )
    (net (code "25") (name "/O5") (class "Default")
      (node (ref "J13") (pin "8") (pinfunction "8_8") (pintype "bidirectional"))
      (node (ref "R22") (pin "2") (pinfunction "2_2") (pintype "passive"))
    )
    (net (code "26") (name "/O6") (class "Default")
      (node (ref "J13") (pin "6") (pinfunction "6_6") (pintype "bidirectional"))
      (node (ref "R23") (pin "2") (pinfunction "2_2") (pintype "passive"))
    )
    (net (code "27") (name "/O7") (class "Default")
      (node (ref "J13") (pin "4") (pinfunction "4_4") (pintype "bidirectional"))
      (node (ref "R24") (pin "2") (pinfunction "2_2") (pintype "passive"))
    )
    (net (code "28") (name "/O8") (class "Default")
      (node (ref "J13") (pin "2") (pinfunction "2_2") (pintype "bidirectional"))
      (node (ref "R25") (pin "2") (pinfunction "2_2") (pintype "passive"))
    )
    (net (code "29") (name "/O9") (class "Default")
      (node (ref "J14") (pin "2") (pinfunction "2_2") (pintype "bidirectional"))
      (node (ref "R33") (pin "2") (pinfunction "2_2") (pintype "passive"))
    )
    (net (code "30") (name "/O10") (class "Default")
      (node (ref "J14") (pin "4") (pinfunction "4_4") (pintype "bidirectional"))
      (node (ref "R32") (pin "2") (pinfunction "2_2") (pintype "passive"))
    )
    (net (code "31") (name "/O11") (class "Default")
      (node (ref "J14") (pin "6") (pinfunction "6_6") (pintype "bidirectional"))
      (node (ref "R31") (pin "2") (pinfunction "2_2") (pintype "passive"))
    )
    (net (code "32") (name "/O12") (class "Default")
      (node (ref "J14") (pin "8") (pinfunction "8_8") (pintype "bidirectional"))
      (node (ref "R30") (pin "2") (pinfunction "2_2") (pintype "passive"))
    )
    (net (code "33") (name "/O13") (class "Default")
      (node (ref "J15") (pin "2") (pinfunction "2_2") (pintype "bidirectional"))
      (node (ref "R29") (pin "2") (pinfunction "2_2") (pintype "passive"))
    )
    (net (code "34") (name "/O14") (class "Default")
      (node (ref "J15") (pin "4") (pinfunction "4_4") (pintype "bidirectional"))
      (node (ref "R28") (pin "2") (pinfunction "2_2") (pintype "passive"))
    )
    (net (code "35") (name "/O15") (class "Default")
      (node (ref "J15") (pin "6") (pinfunction "6_6") (pintype "bidirectional"))
      (node (ref "R27") (pin "2") (pinfunction "2_2") (pintype "passive"))
    )
    (net (code "36") (name "/O16") (class "Default")
      (node (ref "J15") (pin "8") (pinfunction "8_8") (pintype "bidirectional"))
      (node (ref "R26") (pin "2") (pinfunction "2_2") (pintype "passive"))
    )
    (net (code "37") (name "/OSC32_IN") (class "Default")
      (node (ref "C8") (pin "2") (pinfunction "2_2") (pintype "passive"))
      (node (ref "Q2") (pin "2") (pinfunction "2_2") (pintype "passive"))
      (node (ref "U2") (pin "8") (pinfunction "PC14-OSC32_IN_8") (pintype "bidirectional"))
    )
    (net (code "38") (name "/OSC32_OUT") (class "Default")
      (node (ref "C9") (pin "2") (pinfunction "2_2") (pintype "passive"))
      (node (ref "Q2") (pin "1") (pinfunction "1_1") (pintype "passive"))
      (node (ref "U2") (pin "9") (pinfunction "PC15-OSC32_OUT_9") (pintype "bidirectional"))
    )
    (net (code "39") (name "/OSC_IN") (class "Default")
      (node (ref "C6") (pin "2") (pinfunction "2_2") (pintype "passive"))
      (node (ref "Q1") (pin "2") (pinfunction "2_2") (pintype "passive"))
      (node (ref "R7") (pin "2") (pinfunction "2_2") (pintype "passive"))
      (node (ref "U2") (pin "12") (pinfunction "PH0-OSC_IN_12") (pintype "bidirectional"))
    )
    (net (code "40") (name "/OSC_OUT") (class "Default")
      (node (ref "C7") (pin "2") (pinfunction "2_2") (pintype "passive"))
      (node (ref "Q1") (pin "1") (pinfunction "1_1") (pintype "passive"))
      (node (ref "R7") (pin "1") (pinfunction "1_1") (pintype "passive"))
      (node (ref "U2") (pin "13") (pinfunction "PH1-OSC_OUT_13") (pintype "bidirectional"))
    )
    (net (code "41") (name "/PA3") (class "Default")
      (node (ref "J3") (pin "5") (pinfunction "5_5") (pintype "passive"))
      (node (ref "U2") (pin "26") (pinfunction "PA3_26") (pintype "bidirectional"))
    )
    (net (code "42") (name "/PA4") (class "Default")
      (node (ref "J3") (pin "4") (pinfunction "4_4") (pintype "passive"))
      (node (ref "U2") (pin "29") (pinfunction "PA4_29") (pintype "bidirectional"))
    )
    (net (code "43") (name "/PA5") (class "Default")
      (node (ref "J3") (pin "3") (pinfunction "3_3") (pintype "passive"))
      (node (ref "U2") (pin "30") (pinfunction "PA5_30") (pintype "bidirectional"))
    )
    (net (code "44") (name "/PA6") (class "Default")
      (node (ref "J3") (pin "2") (pinfunction "2_2") (pintype "passive"))
      (node (ref "U2") (pin "31") (pinfunction "PA6_31") (pintype "bidirectional"))
      (node (ref "U5") (pin "2") (pinfunction "A1_2") (pintype "bidirectional"))
      (node (ref "U5") (pin "3") (pinfunction "A2_3") (pintype "bidirectional"))
      (node (ref "U5") (pin "4") (pinfunction "A3_4") (pintype "bidirectional"))
      (node (ref "U5") (pin "5") (pinfunction "A4_5") (pintype "bidirectional"))
      (node (ref "U5") (pin "6") (pinfunction "A5_6") (pintype "bidirectional"))
      (node (ref "U5") (pin "7") (pinfunction "A6_7") (pintype "bidirectional"))
      (node (ref "U5") (pin "8") (pinfunction "A7_8") (pintype "bidirectional"))
      (node (ref "U5") (pin "9") (pinfunction "A8_9") (pintype "bidirectional"))
    )
    (net (code "45") (name "/PA8") (class "Default")
      (node (ref "JP10") (pin "1") (pinfunction "1_1") (pintype "passive"))
      (node (ref "U2") (pin "67") (pinfunction "PA8_67") (pintype "bidirectional"))
    )
    (net (code "46") (name "/PA11") (class "Default")
      (node (ref "J7") (pin "2") (pinfunction "2_2") (pintype "passive"))
      (node (ref "U2") (pin "70") (pinfunction "PA11_70") (pintype "bidirectional"))
    )
    (net (code "47") (name "/PA12") (class "Default")
      (node (ref "J7") (pin "3") (pinfunction "3_3") (pintype "passive"))
      (node (ref "U2") (pin "71") (pinfunction "PA12_71") (pintype "bidirectional"))
    )
    (net (code "48") (name "/PC0") (class "Default")
      (node (ref "RN1") (pin "8") (pinfunction "2_8") (pintype "passive"))
      (node (ref "U2") (pin "15") (pinfunction "PC0_15") (pintype "bidirectional"))
    )
    (net (code "49") (name "/PC2") (class "Default")
      (node (ref "RN1") (pin "7") (pinfunction "2_7") (pintype "passive"))
      (node (ref "U2") (pin "17") (pinfunction "PC2_17") (pintype "bidirectional"))
    )
    (net (code "50") (name "/PC3") (class "Default")
      (node (ref "RN1") (pin "6") (pinfunction "2_6") (pintype "passive"))
      (node (ref "U2") (pin "18") (pinfunction "PC3_18") (pintype "bidirectional"))
    )
    (net (code "51") (name "/PD0") (class "Default")
      (node (ref "J9") (pin "1") (pinfunction "1_1") (pintype "passive"))
      (node (ref "U2") (pin "81") (pinfunction "PD0_81") (pintype "bidirectional"))
    )
    (net (code "52") (name "/PE0") (class "Default")
      (node (ref "U2") (pin "97") (pinfunction "PE0_97") (pintype "bidirectional"))
      (node (ref "U3") (pin "2") (pinfunction "A1_2") (pintype "bidirectional"))
    )
    (net (code "53") (name "/PE1") (class "Default")
      (node (ref "U2") (pin "98") (pinfunction "PE1_98") (pintype "bidirectional"))
      (node (ref "U3") (pin "3") (pinfunction "A2_3") (pintype "bidirectional"))
    )
    (net (code "54") (name "/PE2") (class "Default")
      (node (ref "U2") (pin "1") (pinfunction "PE2_1") (pintype "bidirectional"))
      (node (ref "U3") (pin "4") (pinfunction "A3_4") (pintype "bidirectional"))
    )
    (net (code "55") (name "/PE3") (class "Default")
      (node (ref "U2") (pin "2") (pinfunction "PE3_2") (pintype "bidirectional"))
      (node (ref "U3") (pin "5") (pinfunction "A4_5") (pintype "bidirectional"))
    )
    (net (code "56") (name "/PE4") (class "Default")
      (node (ref "U2") (pin "3") (pinfunction "PE4_3") (pintype "bidirectional"))
      (node (ref "U3") (pin "6") (pinfunction "A5_6") (pintype "bidirectional"))
    )
    (net (code "57") (name "/PE5") (class "Default")
      (node (ref "U2") (pin "4") (pinfunction "PE5_4") (pintype "bidirectional"))
      (node (ref "U3") (pin "7") (pinfunction "A6_7") (pintype "bidirectional"))
    )
    (net (code "58") (name "/PE6") (class "Default")
      (node (ref "U2") (pin "5") (pinfunction "PE6_5") (pintype "bidirectional"))
      (node (ref "U3") (pin "8") (pinfunction "A7_8") (pintype "bidirectional"))
    )
    (net (code "59") (name "/PE7") (class "Default")
      (node (ref "U2") (pin "38") (pinfunction "PE7_38") (pintype "bidirectional"))
      (node (ref "U3") (pin "9") (pinfunction "A8_9") (pintype "bidirectional"))
    )
    (net (code "60") (name "/PE8") (class "Default")
      (node (ref "U2") (pin "39") (pinfunction "PE8_39") (pintype "bidirectional"))
      (node (ref "U4") (pin "9") (pinfunction "A8_9") (pintype "bidirectional"))
    )
    (net (code "61") (name "/PE9") (class "Default")
      (node (ref "U2") (pin "40") (pinfunction "PE9_40") (pintype "bidirectional"))
      (node (ref "U4") (pin "8") (pinfunction "A7_8") (pintype "bidirectional"))
    )
    (net (code "62") (name "/PE10") (class "Default")
      (node (ref "U2") (pin "41") (pinfunction "PE10_41") (pintype "bidirectional"))
      (node (ref "U4") (pin "7") (pinfunction "A6_7") (pintype "bidirectional"))
    )
    (net (code "63") (name "/PE11") (class "Default")
      (node (ref "U2") (pin "42") (pinfunction "PE11_42") (pintype "bidirectional"))
      (node (ref "U4") (pin "6") (pinfunction "A5_6") (pintype "bidirectional"))
    )
    (net (code "64") (name "/PE12") (class "Default")
      (node (ref "U2") (pin "43") (pinfunction "PE12_43") (pintype "bidirectional"))
      (node (ref "U4") (pin "5") (pinfunction "A4_5") (pintype "bidirectional"))
    )
    (net (code "65") (name "/PE13") (class "Default")
      (node (ref "U2") (pin "44") (pinfunction "PE13_44") (pintype "bidirectional"))
      (node (ref "U4") (pin "4") (pinfunction "A3_4") (pintype "bidirectional"))
    )
    (net (code "66") (name "/PE14") (class "Default")
      (node (ref "U2") (pin "45") (pinfunction "PE14_45") (pintype "bidirectional"))
      (node (ref "U4") (pin "3") (pinfunction "A2_3") (pintype "bidirectional"))
    )
    (net (code "67") (name "/PE15") (class "Default")
      (node (ref "U2") (pin "46") (pinfunction "PE15_46") (pintype "bidirectional"))
      (node (ref "U4") (pin "2") (pinfunction "A1_2") (pintype "bidirectional"))
    )
    (net (code "68") (name "/RMII_CRS_DV") (class "Default")
      (node (ref "SV1") (pin "8") (pinfunction "8_8") (pintype "passive"))
      (node (ref "U2") (pin "32") (pinfunction "PA7_32") (pintype "bidirectional"))
    )
    (net (code "69") (name "/RMII_INT") (class "Default")
      (node (ref "U2") (pin "35") (pinfunction "PB0_35") (pintype "bidirectional"))
    )
    (net (code "70") (name "/RMII_REF_CLK") (class "Default")
      (node (ref "JP10") (pin "2") (pinfunction "2_2") (pintype "passive"))
      (node (ref "SV1") (pin "7") (pinfunction "7_7") (pintype "passive"))
      (node (ref "U2") (pin "24") (pinfunction "PA1_24") (pintype "bidirectional"))
    )
    (net (code "71") (name "/RMII_RXD0") (class "Default")
      (node (ref "SV1") (pin "5") (pinfunction "5_5") (pintype "passive"))
      (node (ref "U2") (pin "33") (pinfunction "PC4_33") (pintype "bidirectional"))
    )
    (net (code "72") (name "/RMII_RXD1") (class "Default")
      (node (ref "SV1") (pin "6") (pinfunction "6_6") (pintype "passive"))
      (node (ref "U2") (pin "34") (pinfunction "PC5_34") (pintype "bidirectional"))
    )
    (net (code "73") (name "/RMII_TXD0") (class "Default")
      (node (ref "SV1") (pin "4") (pinfunction "4_4") (pintype "passive"))
      (node (ref "U2") (pin "51") (pinfunction "PB12_51") (pintype "bidirectional"))
    )
    (net (code "74") (name "/RMII_TXD1") (class "Default")
      (node (ref "SV1") (pin "1") (pinfunction "1_1") (pintype "passive"))
      (node (ref "U2") (pin "52") (pinfunction "PB13_52") (pintype "bidirectional"))
    )
    (net (code "75") (name "/RMII_TX_EN") (class "Default")
      (node (ref "SV1") (pin "3") (pinfunction "3_3") (pintype "passive"))
      (node (ref "U2") (pin "48") (pinfunction "PB11_48") (pintype "bidirectional"))
    )
    (net (code "76") (name "/SDIO_CK") (class "Default")
      (node (ref "JP9") (pin "2") (pinfunction "2_2") (pintype "passive"))
      (node (ref "U2") (pin "80") (pinfunction "PC12_80") (pintype "bidirectional"))
    )
    (net (code "77") (name "/SDIO_CMD") (class "Default")
      (node (ref "JP9") (pin "1") (pinfunction "1_1") (pintype "passive"))
      (node (ref "U2") (pin "83") (pinfunction "PD2_83") (pintype "bidirectional"))
    )
    (net (code "78") (name "/SDIO_D0") (class "Default")
      (node (ref "JP9") (pin "3") (pinfunction "3_3") (pintype "passive"))
      (node (ref "U2") (pin "65") (pinfunction "PC8_65") (pintype "bidirectional"))
    )
    (net (code "79") (name "/SDIO_D1") (class "Default")
      (node (ref "JP9") (pin "4") (pinfunction "4_4") (pintype "passive"))
      (node (ref "U2") (pin "66") (pinfunction "PC9_66") (pintype "bidirectional"))
    )
    (net (code "80") (name "/SDIO_D2") (class "Default")
      (node (ref "JP9") (pin "5") (pinfunction "5_5") (pintype "passive"))
      (node (ref "U2") (pin "78") (pinfunction "PC10_78") (pintype "bidirectional"))
    )
    (net (code "81") (name "/SDIO_D3") (class "Default")
      (node (ref "JP9") (pin "6") (pinfunction "6_6") (pintype "passive"))
      (node (ref "U2") (pin "79") (pinfunction "PC11_79") (pintype "bidirectional"))
    )
    (net (code "82") (name "/SPI2_MISO") (class "Default")
      (node (ref "J8") (pin "5") (pinfunction "5_5") (pintype "passive"))
      (node (ref "U2") (pin "90") (pinfunction "PB4_90") (pintype "bidirectional"))
    )
    (net (code "83") (name "/SPI2_MOSI") (class "Default")
      (node (ref "J8") (pin "6") (pinfunction "6_6") (pintype "passive"))
      (node (ref "U2") (pin "91") (pinfunction "PB5_91") (pintype "bidirectional"))
    )
    (net (code "84") (name "/SPI2_NSS") (class "Default")
      (node (ref "J8") (pin "3") (pinfunction "3_3") (pintype "passive"))
      (node (ref "U2") (pin "77") (pinfunction "PA15_77") (pintype "bidirectional"))
    )
    (net (code "85") (name "/SPI2_SCK") (class "Default")
      (node (ref "J8") (pin "4") (pinfunction "4_4") (pintype "passive"))
      (node (ref "U2") (pin "89") (pinfunction "PB3_89") (pintype "bidirectional"))
    )
    (net (code "86") (name "/SWCLK") (class "Default")
      (node (ref "J7") (pin "5") (pinfunction "5_5") (pintype "passive"))
      (node (ref "U2") (pin "76") (pinfunction "PA14_76") (pintype "bidirectional"))
    )
    (net (code "87") (name "/SWDIO") (class "Default")
      (node (ref "J7") (pin "4") (pinfunction "4_4") (pintype "passive"))
      (node (ref "U2") (pin "72") (pinfunction "PA13_72") (pintype "bidirectional"))
    )
    (net (code "88") (name "/USART0_RX") (class "Default")
      (node (ref "J5") (pin "2") (pinfunction "2_2") (pintype "passive"))
      (node (ref "U2") (pin "93") (pinfunction "PB7_93") (pintype "bidirectional"))
    )
    (net (code "89") (name "/USART0_TX") (class "Default")
      (node (ref "J5") (pin "3") (pinfunction "3_3") (pintype "passive"))
      (node (ref "U2") (pin "92") (pinfunction "PB6_92") (pintype "bidirectional"))
    )
    (net (code "90") (name "/USART1_RX") (class "Default")
      (node (ref "J9") (pin "4") (pinfunction "4_4") (pintype "passive"))
      (node (ref "U2") (pin "87") (pinfunction "PD6_87") (pintype "bidirectional"))
    )
    (net (code "91") (name "/USART1_TX") (class "Default")
      (node (ref "J9") (pin "5") (pinfunction "5_5") (pintype "passive"))
      (node (ref "U2") (pin "86") (pinfunction "PD5_86") (pintype "bidirectional"))
    )
    (net (code "92") (name "/USART2_RX") (class "Default")
      (node (ref "J2") (pin "2") (pinfunction "2_2") (pintype "passive"))
      (node (ref "U2") (pin "56") (pinfunction "PD9_56") (pintype "bidirectional"))
    )
    (net (code "93") (name "/USART2_TX") (class "Default")
      (node (ref "J2") (pin "3") (pinfunction "3_3") (pintype "passive"))
      (node (ref "R35") (pin "1") (pinfunction "1_1") (pintype "passive"))
      (node (ref "U2") (pin "55") (pinfunction "PD8_55") (pintype "bidirectional"))
    )
    (net (code "94") (name "/USART5_RX") (class "Default")
      (node (ref "J6") (pin "2") (pinfunction "2_2") (pintype "passive"))
      (node (ref "U2") (pin "64") (pinfunction "PC7_64") (pintype "bidirectional"))
    )
    (net (code "95") (name "/USART5_TX") (class "Default")
      (node (ref "J6") (pin "3") (pinfunction "3_3") (pintype "passive"))
      (node (ref "R34") (pin "1") (pinfunction "1_1") (pintype "passive"))
      (node (ref "U2") (pin "63") (pinfunction "PC6_63") (pintype "bidirectional"))
    )
    (net (code "96") (name "/VBAT") (class "Default")
      (node (ref "C12") (pin "1") (pinfunction "1_1") (pintype "passive"))
      (node (ref "C14") (pin "+") (pinfunction "+_+") (pintype "passive"))
      (node (ref "D1") (pin "C") (pinfunction "C_C") (pintype "passive"))
      (node (ref "J11") (pin "2") (pinfunction "2_2") (pintype "passive"))
      (node (ref "U2") (pin "6") (pinfunction "VBAT_6") (pintype "power_in"))
    )
    (net (code "97") (name "GND") (class "Default")
      (node (ref "C1") (pin "-") (pinfunction "-_-") (pintype "passive"))
      (node (ref "C10") (pin "2") (pinfunction "2_2") (pintype "passive"))
      (node (ref "C11") (pin "2") (pinfunction "2_2") (pintype "passive"))
      (node (ref "C12") (pin "2") (pinfunction "2_2") (pintype "passive"))
      (node (ref "C13") (pin "2") (pinfunction "2_2") (pintype "passive"))
      (node (ref "C14") (pin "-") (pinfunction "-_-") (pintype "passive"))
      (node (ref "C15") (pin "2") (pinfunction "2_2") (pintype "passive"))
      (node (ref "C16") (pin "2") (pinfunction "2_2") (pintype "passive"))
      (node (ref "C17") (pin "2") (pinfunction "2_2") (pintype "passive"))
      (node (ref "C18") (pin "2") (pinfunction "2_2") (pintype "passive"))
      (node (ref "C19") (pin "2") (pinfunction "2_2") (pintype "passive"))
      (node (ref "C2") (pin "2") (pinfunction "2_2") (pintype "passive"))
      (node (ref "C20") (pin "2") (pinfunction "2_2") (pintype "passive"))
      (node (ref "C21") (pin "2") (pinfunction "2_2") (pintype "passive"))
      (node (ref "C22") (pin "2") (pinfunction "2_2") (pintype "passive"))
      (node (ref "C23") (pin "2") (pinfunction "2_2") (pintype "passive"))
      (node (ref "C24") (pin "-") (pinfunction "-_-") (pintype "passive"))
      (node (ref "C25") (pin "2") (pinfunction "2_2") (pintype "passive"))
      (node (ref "C26") (pin "2") (pinfunction "2_2") (pintype "passive"))
      (node (ref "C27") (pin "2") (pinfunction "2_2") (pintype "passive"))
      (node (ref "C28") (pin "2") (pinfunction "2_2") (pintype "passive"))
      (node (ref "C29") (pin "2") (pinfunction "2_2") (pintype "passive"))
      (node (ref "C3") (pin "-") (pinfunction "-_-") (pintype "passive"))
      (node (ref "C30") (pin "2") (pinfunction "2_2") (pintype "passive"))
      (node (ref "C4") (pin "2") (pinfunction "2_2") (pintype "passive"))
      (node (ref "C5") (pin "2") (pinfunction "2_2") (pintype "passive"))
      (node (ref "C6") (pin "1") (pinfunction "1_1") (pintype "passive"))
      (node (ref "C7") (pin "1") (pinfunction "1_1") (pintype "passive"))
      (node (ref "C8") (pin "1") (pinfunction "1_1") (pintype "passive"))
      (node (ref "C9") (pin "1") (pinfunction "1_1") (pintype "passive"))
      (node (ref "IC1") (pin "1") (pinfunction "A0_1") (pintype "input"))
      (node (ref "IC1") (pin "2") (pinfunction "A1_2") (pintype "input"))
      (node (ref "IC1") (pin "3") (pinfunction "A2_3") (pintype "input"))
      (node (ref "IC1") (pin "4") (pinfunction "GND_4") (pintype "power_in"))
      (node (ref "IC1") (pin "7") (pinfunction "WP_7") (pintype "input"))
      (node (ref "J1") (pin "1") (pinfunction "1_1") (pintype "passive"))
      (node (ref "J11") (pin "1") (pinfunction "1_1") (pintype "passive"))
      (node (ref "J12") (pin "1") (pinfunction "1_1") (pintype "bidirectional"))
      (node (ref "J12") (pin "3") (pinfunction "3_3") (pintype "bidirectional"))
      (node (ref "J12") (pin "5") (pinfunction "5_5") (pintype "bidirectional"))
      (node (ref "J12") (pin "7") (pinfunction "7_7") (pintype "bidirectional"))
      (node (ref "J13") (pin "1") (pinfunction "1_1") (pintype "bidirectional"))
      (node (ref "J13") (pin "3") (pinfunction "3_3") (pintype "bidirectional"))
      (node (ref "J13") (pin "5") (pinfunction "5_5") (pintype "bidirectional"))
      (node (ref "J13") (pin "7") (pinfunction "7_7") (pintype "bidirectional"))
      (node (ref "J14") (pin "1") (pinfunction "1_1") (pintype "bidirectional"))
      (node (ref "J14") (pin "3") (pinfunction "3_3") (pintype "bidirectional"))
      (node (ref "J14") (pin "5") (pinfunction "5_5") (pintype "bidirectional"))
      (node (ref "J14") (pin "7") (pinfunction "7_7") (pintype "bidirectional"))
      (node (ref "J15") (pin "1") (pinfunction "1_1") (pintype "bidirectional"))
      (node (ref "J15") (pin "3") (pinfunction "3_3") (pintype "bidirectional"))
      (node (ref "J15") (pin "5") (pinfunction "5_5") (pintype "bidirectional"))
      (node (ref "J15") (pin "7") (pinfunction "7_7") (pintype "bidirectional"))
      (node (ref "J2") (pin "1") (pinfunction "1_1") (pintype "passive"))
      (node (ref "J3") (pin "1") (pinfunction "1_1") (pintype "passive"))
      (node (ref "J4") (pin "1") (pinfunction "1_1") (pintype "passive"))
      (node (ref "J5") (pin "1") (pinfunction "1_1") (pintype "passive"))
      (node (ref "J6") (pin "1") (pinfunction "1_1") (pintype "passive"))
      (node (ref "J7") (pin "1") (pinfunction "1_1") (pintype "passive"))
      (node (ref "J8") (pin "2") (pinfunction "2_2") (pintype "passive"))
      (node (ref "J9") (pin "3") (pinfunction "3_3") (pintype "passive"))
      (node (ref "JP1") (pin "1") (pinfunction "1_1") (pintype "passive"))
      (node (ref "JP2") (pin "1") (pinfunction "1_1") (pintype "passive"))
      (node (ref "JP3") (pin "1") (pinfunction "1_1") (pintype "passive"))
      (node (ref "JP4") (pin "1") (pinfunction "1_1") (pintype "passive"))
      (node (ref "JP5") (pin "1") (pinfunction "1_1") (pintype "passive"))
      (node (ref "JP6") (pin "1") (pinfunction "1_1") (pintype "passive"))
      (node (ref "JP7") (pin "1") (pinfunction "1_1") (pintype "passive"))
      (node (ref "JP8") (pin "1") (pinfunction "1_1") (pintype "passive"))
      (node (ref "JP9") (pin "7") (pinfunction "7_7") (pintype "passive"))
      (node (ref "LED1") (pin "C") (pinfunction "C_C") (pintype "passive"))
      (node (ref "LED2") (pin "C") (pinfunction "C_C") (pintype "passive"))
      (node (ref "LED3") (pin "C") (pinfunction "C_C") (pintype "passive"))
      (node (ref "LED4") (pin "C") (pinfunction "C_C") (pintype "passive"))
      (node (ref "R2") (pin "1") (pinfunction "1_1") (pintype "passive"))
      (node (ref "R3") (pin "2") (pinfunction "2_2") (pintype "passive"))
      (node (ref "R8") (pin "1") (pinfunction "1_1") (pintype "passive"))
      (node (ref "R9") (pin "1") (pinfunction "1_1") (pintype "passive"))
      (node (ref "SV1") (pin "11") (pinfunction "11_11") (pintype "passive"))
      (node (ref "SV1") (pin "12") (pinfunction "12_12") (pintype "passive"))
      (node (ref "SW1") (pin "A") (pinfunction "P_A") (pintype "passive"))
      (node (ref "SW1") (pin "A'") (pinfunction "P1_A'") (pintype "passive"))
      (node (ref "SW3") (pin "A") (pinfunction "P_A") (pintype "passive"))
      (node (ref "SW3") (pin "A'") (pinfunction "P1_A'") (pintype "passive"))
      (node (ref "U1") (pin "1") (pinfunction "ADJ/GND_1") (pintype "power_in"))
      (node (ref "U2") (pin "10") (pinfunction "VSS_2_10") (pintype "passive"))
      (node (ref "U2") (pin "20") (pinfunction "VSSA_20") (pintype "passive"))
      (node (ref "U2") (pin "27") (pinfunction "VSS_3_27") (pintype "passive"))
      (node (ref "U2") (pin "74") (pinfunction "VSS_4_74") (pintype "passive"))
      (node (ref "U2") (pin "99") (pinfunction "VSS_99") (pintype "passive"))
      (node (ref "U3") (pin "10") (pinfunction "GND_10") (pintype "power_in"))
      (node (ref "U3") (pin "19") (pinfunction "~{OE}_19") (pintype "input"))
      (node (ref "U4") (pin "10") (pinfunction "GND_10") (pintype "power_in"))
      (node (ref "U4") (pin "19") (pinfunction "~{OE}_19") (pintype "input"))
      (node (ref "U5") (pin "10") (pinfunction "GND_10") (pintype "power_in"))
      (node (ref "U5") (pin "19") (pinfunction "~{OE}_19") (pintype "input"))
      (node (ref "V1") (pin "1") (pinfunction "-VIN_1") (pintype "passive"))
      (node (ref "X1") (pin "1") (pinfunction "KL_1") (pintype "passive"))
    )
    (net (code "98") (name "GND-ISO") (class "Default")
      (node (ref "C31") (pin "2") (pinfunction "2_2") (pintype "passive"))
      (node (ref "C32") (pin "2") (pinfunction "2_2") (pintype "passive"))
      (node (ref "C33") (pin "2") (pinfunction "2_2") (pintype "passive"))
      (node (ref "C34") (pin "2") (pinfunction "2_2") (pintype "passive"))
      (node (ref "D2") (pin "3") (pinfunction "3_3") (pintype "power_in"))
      (node (ref "D3") (pin "3") (pinfunction "3_3") (pintype "power_in"))
      (node (ref "IC2") (pin "5") (pinfunction "GND_5") (pintype "power_in"))
      (node (ref "IC3") (pin "5") (pinfunction "GND_5") (pintype "power_in"))
      (node (ref "OK1") (pin "5") (pinfunction "GND_5") (pintype "passive"))
      (node (ref "OK2") (pin "5") (pinfunction "GND_5") (pintype "passive"))
      (node (ref "V1") (pin "3") (pinfunction "-VOUT_3") (pintype "passive"))
      (node (ref "X2") (pin "1") (pinfunction "KL_1") (pintype "passive"))
      (node (ref "X3") (pin "1") (pinfunction "KL_1") (pintype "passive"))
    )
    (net (code "99") (name "Net-(IC2-A)") (class "Default")
      (node (ref "D2") (pin "1") (pinfunction "1_1") (pintype "passive"))
      (node (ref "IC2") (pin "6") (pinfunction "A_6") (pintype "output"))
      (node (ref "R38") (pin "1") (pinfunction "1_1") (pintype "passive"))
      (node (ref "X2") (pin "2") (pinfunction "KL_2") (pintype "passive"))
    )
    (net (code "100") (name "Net-(IC2-B)") (class "Default")
      (node (ref "D2") (pin "2") (pinfunction "2_2") (pintype "passive"))
      (node (ref "IC2") (pin "7") (pinfunction "B_7") (pintype "output"))
      (node (ref "R38") (pin "2") (pinfunction "2_2") (pintype "passive"))
      (node (ref "X2") (pin "3") (pinfunction "KL_3") (pintype "passive"))
    )
    (net (code "101") (name "Net-(IC2-D)") (class "Default")
      (node (ref "IC2") (pin "4") (pinfunction "D_4") (pintype "input"))
      (node (ref "OK1") (pin "6") (pinfunction "VO_6") (pintype "passive"))
      (node (ref "R36") (pin "2") (pinfunction "2_2") (pintype "passive"))
    )
    (net (code "102") (name "Net-(IC3-A)") (class "Default")
      (node (ref "D3") (pin "1") (pinfunction "1_1") (pintype "passive"))
      (node (ref "IC3") (pin "6") (pinfunction "A_6") (pintype "output"))
      (node (ref "R39") (pin "1") (pinfunction "1_1") (pintype "passive"))
      (node (ref "X3") (pin "2") (pinfunction "KL_2") (pintype "passive"))
    )
    (net (code "103") (name "Net-(IC3-B)") (class "Default")
      (node (ref "D3") (pin "2") (pinfunction "2_2") (pintype "passive"))
      (node (ref "IC3") (pin "7") (pinfunction "B_7") (pintype "output"))
      (node (ref "R39") (pin "2") (pinfunction "2_2") (pintype "passive"))
      (node (ref "X3") (pin "3") (pinfunction "KL_3") (pintype "passive"))
    )
    (net (code "104") (name "Net-(IC3-D)") (class "Default")
      (node (ref "IC3") (pin "4") (pinfunction "D_4") (pintype "input"))
      (node (ref "OK2") (pin "6") (pinfunction "VO_6") (pintype "passive"))
      (node (ref "R37") (pin "2") (pinfunction "2_2") (pintype "passive"))
    )
    (net (code "105") (name "Net-(LED1-PadA)") (class "Default")
      (node (ref "LED1") (pin "A") (pinfunction "A_A") (pintype "passive"))
      (node (ref "RN1") (pin "1") (pinfunction "1_1") (pintype "passive"))
    )
    (net (code "106") (name "Net-(OK1-C)") (class "Default")
      (node (ref "OK1") (pin "3") (pinfunction "C_3") (pintype "passive"))
      (node (ref "R34") (pin "2") (pinfunction "2_2") (pintype "passive"))
    )
    (net (code "107") (name "Net-(OK2-C)") (class "Default")
      (node (ref "OK2") (pin "3") (pinfunction "C_3") (pintype "passive"))
      (node (ref "R35") (pin "2") (pinfunction "2_2") (pintype "passive"))
    )
    (net (code "108") (name "Net-(Q3-D)") (class "Default")
      (node (ref "Q3") (pin "3") (pinfunction "D_3") (pintype "passive"))
      (node (ref "Q4") (pin "6") (pinfunction "E1_6") (pintype "passive"))
      (node (ref "X1") (pin "2") (pinfunction "KL_2") (pintype "passive"))
    )
    (net (code "109") (name "Net-(Q3-G)") (class "Default")
      (node (ref "Q3") (pin "1") (pinfunction "G_1") (pintype "passive"))
      (node (ref "Q4") (pin "4") (pinfunction "C2_4") (pintype "passive"))
      (node (ref "R9") (pin "2") (pinfunction "2_2") (pintype "passive"))
    )
    (net (code "110") (name "Net-(Q4A-B1)") (class "Default")
      (node (ref "Q4") (pin "1") (pinfunction "C1_1") (pintype "passive"))
      (node (ref "Q4") (pin "2") (pinfunction "B1_2") (pintype "passive"))
      (node (ref "Q4") (pin "3") (pinfunction "B2_3") (pintype "passive"))
      (node (ref "R8") (pin "2") (pinfunction "2_2") (pintype "passive"))
    )
    (net (code "111") (name "Net-(RN1B-1)") (class "Default")
      (node (ref "LED2") (pin "A") (pinfunction "A_A") (pintype "passive"))
      (node (ref "RN1") (pin "2") (pinfunction "1_2") (pintype "passive"))
    )
    (net (code "112") (name "Net-(RN1C-1)") (class "Default")
      (node (ref "LED3") (pin "A") (pinfunction "A_A") (pintype "passive"))
      (node (ref "RN1") (pin "3") (pinfunction "1_3") (pintype "passive"))
    )
    (net (code "113") (name "Net-(RN1D-1)") (class "Default")
      (node (ref "LED4") (pin "A") (pinfunction "A_A") (pintype "passive"))
      (node (ref "RN1") (pin "4") (pinfunction "1_4") (pintype "passive"))
    )
    (net (code "114") (name "Net-(U3-B1)") (class "Default")
      (node (ref "R18") (pin "1") (pinfunction "1_1") (pintype "passive"))
      (node (ref "U3") (pin "18") (pinfunction "B1_18") (pintype "bidirectional"))
    )
    (net (code "115") (name "Net-(U3-B2)") (class "Default")
      (node (ref "R19") (pin "1") (pinfunction "1_1") (pintype "passive"))
      (node (ref "U3") (pin "17") (pinfunction "B2_17") (pintype "bidirectional"))
    )
    (net (code "116") (name "Net-(U3-B3)") (class "Default")
      (node (ref "R20") (pin "1") (pinfunction "1_1") (pintype "passive"))
      (node (ref "U3") (pin "16") (pinfunction "B3_16") (pintype "bidirectional"))
    )
    (net (code "117") (name "Net-(U3-B4)") (class "Default")
      (node (ref "R21") (pin "1") (pinfunction "1_1") (pintype "passive"))
      (node (ref "U3") (pin "15") (pinfunction "B4_15") (pintype "bidirectional"))
    )
    (net (code "118") (name "Net-(U3-B5)") (class "Default")
      (node (ref "R22") (pin "1") (pinfunction "1_1") (pintype "passive"))
      (node (ref "U3") (pin "14") (pinfunction "B5_14") (pintype "bidirectional"))
    )
    (net (code "119") (name "Net-(U3-B6)") (class "Default")
      (node (ref "R23") (pin "1") (pinfunction "1_1") (pintype "passive"))
      (node (ref "U3") (pin "13") (pinfunction "B6_13") (pintype "bidirectional"))
    )
    (net (code "120") (name "Net-(U3-B7)") (class "Default")
      (node (ref "R24") (pin "1") (pinfunction "1_1") (pintype "passive"))
      (node (ref "U3") (pin "12") (pinfunction "B7_12") (pintype "bidirectional"))
    )
    (net (code "121") (name "Net-(U3-B8)") (class "Default")
      (node (ref "R25") (pin "1") (pinfunction "1_1") (pintype "passive"))
      (node (ref "U3") (pin "11") (pinfunction "B8_11") (pintype "bidirectional"))
    )
    (net (code "122") (name "Net-(U4-B1)") (class "Default")
      (node (ref "R26") (pin "1") (pinfunction "1_1") (pintype "passive"))
      (node (ref "U4") (pin "18") (pinfunction "B1_18") (pintype "bidirectional"))
    )
    (net (code "123") (name "Net-(U4-B2)") (class "Default")
      (node (ref "R27") (pin "1") (pinfunction "1_1") (pintype "passive"))
      (node (ref "U4") (pin "17") (pinfunction "B2_17") (pintype "bidirectional"))
    )
    (net (code "124") (name "Net-(U4-B3)") (class "Default")
      (node (ref "R28") (pin "1") (pinfunction "1_1") (pintype "passive"))
      (node (ref "U4") (pin "16") (pinfunction "B3_16") (pintype "bidirectional"))
    )
    (net (code "125") (name "Net-(U4-B4)") (class "Default")
      (node (ref "R29") (pin "1") (pinfunction "1_1") (pintype "passive"))
      (node (ref "U4") (pin "15") (pinfunction "B4_15") (pintype "bidirectional"))
    )
    (net (code "126") (name "Net-(U4-B5)") (class "Default")
      (node (ref "R30") (pin "1") (pinfunction "1_1") (pintype "passive"))
      (node (ref "U4") (pin "14") (pinfunction "B5_14") (pintype "bidirectional"))
    )
    (net (code "127") (name "Net-(U4-B6)") (class "Default")
      (node (ref "R31") (pin "1") (pinfunction "1_1") (pintype "passive"))
      (node (ref "U4") (pin "13") (pinfunction "B6_13") (pintype "bidirectional"))
    )
    (net (code "128") (name "Net-(U4-B7)") (class "Default")
      (node (ref "R32") (pin "1") (pinfunction "1_1") (pintype "passive"))
      (node (ref "U4") (pin "12") (pinfunction "B7_12") (pintype "bidirectional"))
    )
    (net (code "129") (name "Net-(U4-B8)") (class "Default")
      (node (ref "R33") (pin "1") (pinfunction "1_1") (pintype "passive"))
      (node (ref "U4") (pin "11") (pinfunction "B8_11") (pintype "bidirectional"))
    )
    (net (code "130") (name "Net-(U5-B1)") (class "Default")
      (node (ref "R10") (pin "1") (pinfunction "1_1") (pintype "passive"))
      (node (ref "U5") (pin "18") (pinfunction "B1_18") (pintype "bidirectional"))
    )
    (net (code "131") (name "Net-(U5-B2)") (class "Default")
      (node (ref "R11") (pin "1") (pinfunction "1_1") (pintype "passive"))
      (node (ref "U5") (pin "17") (pinfunction "B2_17") (pintype "bidirectional"))
    )
    (net (code "132") (name "Net-(U5-B3)") (class "Default")
      (node (ref "R12") (pin "1") (pinfunction "1_1") (pintype "passive"))
      (node (ref "U5") (pin "16") (pinfunction "B3_16") (pintype "bidirectional"))
    )
    (net (code "133") (name "Net-(U5-B4)") (class "Default")
      (node (ref "R13") (pin "1") (pinfunction "1_1") (pintype "passive"))
      (node (ref "U5") (pin "15") (pinfunction "B4_15") (pintype "bidirectional"))
    )
    (net (code "134") (name "Net-(U5-B5)") (class "Default")
      (node (ref "R14") (pin "1") (pinfunction "1_1") (pintype "passive"))
      (node (ref "U5") (pin "14") (pinfunction "B5_14") (pintype "bidirectional"))
    )
    (net (code "135") (name "Net-(U5-B6)") (class "Default")
      (node (ref "R15") (pin "1") (pinfunction "1_1") (pintype "passive"))
      (node (ref "U5") (pin "13") (pinfunction "B6_13") (pintype "bidirectional"))
    )
    (net (code "136") (name "Net-(U5-B7)") (class "Default")
      (node (ref "R16") (pin "1") (pinfunction "1_1") (pintype "passive"))
      (node (ref "U5") (pin "12") (pinfunction "B7_12") (pintype "bidirectional"))
    )
    (net (code "137") (name "Net-(U5-B8)") (class "Default")
      (node (ref "R17") (pin "1") (pinfunction "1_1") (pintype "passive"))
      (node (ref "U5") (pin "11") (pinfunction "B8_11") (pintype "bidirectional"))
    )
    (net (code "138") (name "VCC") (class "Default")
      (node (ref "C31") (pin "1") (pinfunction "1_1") (pintype "passive"))
      (node (ref "C32") (pin "1") (pinfunction "1_1") (pintype "passive"))
      (node (ref "C33") (pin "1") (pinfunction "1_1") (pintype "passive"))
      (node (ref "C34") (pin "1") (pinfunction "1_1") (pintype "passive"))
      (node (ref "IC2") (pin "2") (pinfunction "~{RE}_2") (pintype "input"))
      (node (ref "IC2") (pin "3") (pinfunction "DE_3") (pintype "input"))
      (node (ref "IC2") (pin "8") (pinfunction "VCC_8") (pintype "power_in"))
      (node (ref "IC3") (pin "2") (pinfunction "~{RE}_2") (pintype "input"))
      (node (ref "IC3") (pin "3") (pinfunction "DE_3") (pintype "input"))
      (node (ref "IC3") (pin "8") (pinfunction "VCC_8") (pintype "power_in"))
      (node (ref "OK1") (pin "8") (pinfunction "VCC_8") (pintype "passive"))
      (node (ref "OK2") (pin "8") (pinfunction "VCC_8") (pintype "passive"))
      (node (ref "R36") (pin "1") (pinfunction "1_1") (pintype "passive"))
      (node (ref "R37") (pin "1") (pinfunction "1_1") (pintype "passive"))
      (node (ref "V1") (pin "4") (pinfunction "+VOUT_4") (pintype "passive"))
    )
    (net (code "139") (name "unconnected-(IC2-R-Pad1)") (class "Default")
      (node (ref "IC2") (pin "1") (pinfunction "R_1") (pintype "input"))
    )
    (net (code "140") (name "unconnected-(IC3-R-Pad1)") (class "Default")
      (node (ref "IC3") (pin "1") (pinfunction "R_1") (pintype "input"))
    )
    (net (code "141") (name "unconnected-(OK1-VE-Pad7)") (class "Default")
      (node (ref "OK1") (pin "7") (pinfunction "VE_7") (pintype "passive"))
    )
    (net (code "142") (name "unconnected-(OK2-VE-Pad7)") (class "Default")
      (node (ref "OK2") (pin "7") (pinfunction "VE_7") (pintype "passive"))
    )
    (net (code "143") (name "unconnected-(SV1-Pad2)") (class "Default")
      (node (ref "SV1") (pin "2") (pinfunction "2_2") (pintype "passive"))
    )
    (net (code "144") (name "unconnected-(U2-NC-Pad73)") (class "Default")
      (node (ref "U2") (pin "73") (pinfunction "NC_73") (pintype "no_connect"))
    )
    (net (code "145") (name "unconnected-(U2-NC_2-Pad49)") (class "Default")
      (node (ref "U2") (pin "49") (pinfunction "NC_2_49") (pintype "no_connect"))
    )
    (net (code "146") (name "unconnected-(U2-PA0-WKUP-Pad23)") (class "Default")
      (node (ref "U2") (pin "23") (pinfunction "PA0-WKUP_23") (pintype "bidirectional"))
    )
    (net (code "147") (name "unconnected-(U2-PB1-Pad36)") (class "Default")
      (node (ref "U2") (pin "36") (pinfunction "PB1_36") (pintype "bidirectional"))
    )
    (net (code "148") (name "unconnected-(U2-PB10-Pad47)") (class "Default")
      (node (ref "U2") (pin "47") (pinfunction "PB10_47") (pintype "bidirectional"))
    )
    (net (code "149") (name "unconnected-(U2-PB14-Pad53)") (class "Default")
      (node (ref "U2") (pin "53") (pinfunction "PB14_53") (pintype "bidirectional"))
    )
    (net (code "150") (name "unconnected-(U2-PB15-Pad54)") (class "Default")
      (node (ref "U2") (pin "54") (pinfunction "PB15_54") (pintype "bidirectional"))
    )
    (net (code "151") (name "unconnected-(U2-PD1-Pad82)") (class "Default")
      (node (ref "U2") (pin "82") (pinfunction "PD1_82") (pintype "bidirectional"))
    )
    (net (code "152") (name "unconnected-(U2-PD3-Pad84)") (class "Default")
      (node (ref "U2") (pin "84") (pinfunction "PD3_84") (pintype "bidirectional"))
    )
    (net (code "153") (name "unconnected-(U2-PD4-Pad85)") (class "Default")
      (node (ref "U2") (pin "85") (pinfunction "PD4_85") (pintype "bidirectional"))
    )
    (net (code "154") (name "unconnected-(U2-PD7-Pad88)") (class "Default")
      (node (ref "U2") (pin "88") (pinfunction "PD7_88") (pintype "bidirectional"))
    )
    (net (code "155") (name "unconnected-(U2-PD10-Pad57)") (class "Default")
      (node (ref "U2") (pin "57") (pinfunction "PD10_57") (pintype "bidirectional"))
    )
    (net (code "156") (name "unconnected-(U2-PD11-Pad58)") (class "Default")
      (node (ref "U2") (pin "58") (pinfunction "PD11_58") (pintype "bidirectional"))
    )
    (net (code "157") (name "unconnected-(U2-PD12-Pad59)") (class "Default")
      (node (ref "U2") (pin "59") (pinfunction "PD12_59") (pintype "bidirectional"))
    )
    (net (code "158") (name "unconnected-(U2-PD13-Pad60)") (class "Default")
      (node (ref "U2") (pin "60") (pinfunction "PD13_60") (pintype "bidirectional"))
    )
    (net (code "159") (name "unconnected-(U2-PD14-Pad61)") (class "Default")
      (node (ref "U2") (pin "61") (pinfunction "PD14_61") (pintype "bidirectional"))
    )
    (net (code "160") (name "unconnected-(U2-PD15-Pad62)") (class "Default")
      (node (ref "U2") (pin "62") (pinfunction "PD15_62") (pintype "bidirectional"))
    )
  )
)
